# ADAS_ECU_revA.net
KiCad netlist of a schematic drawn in Altium Designer
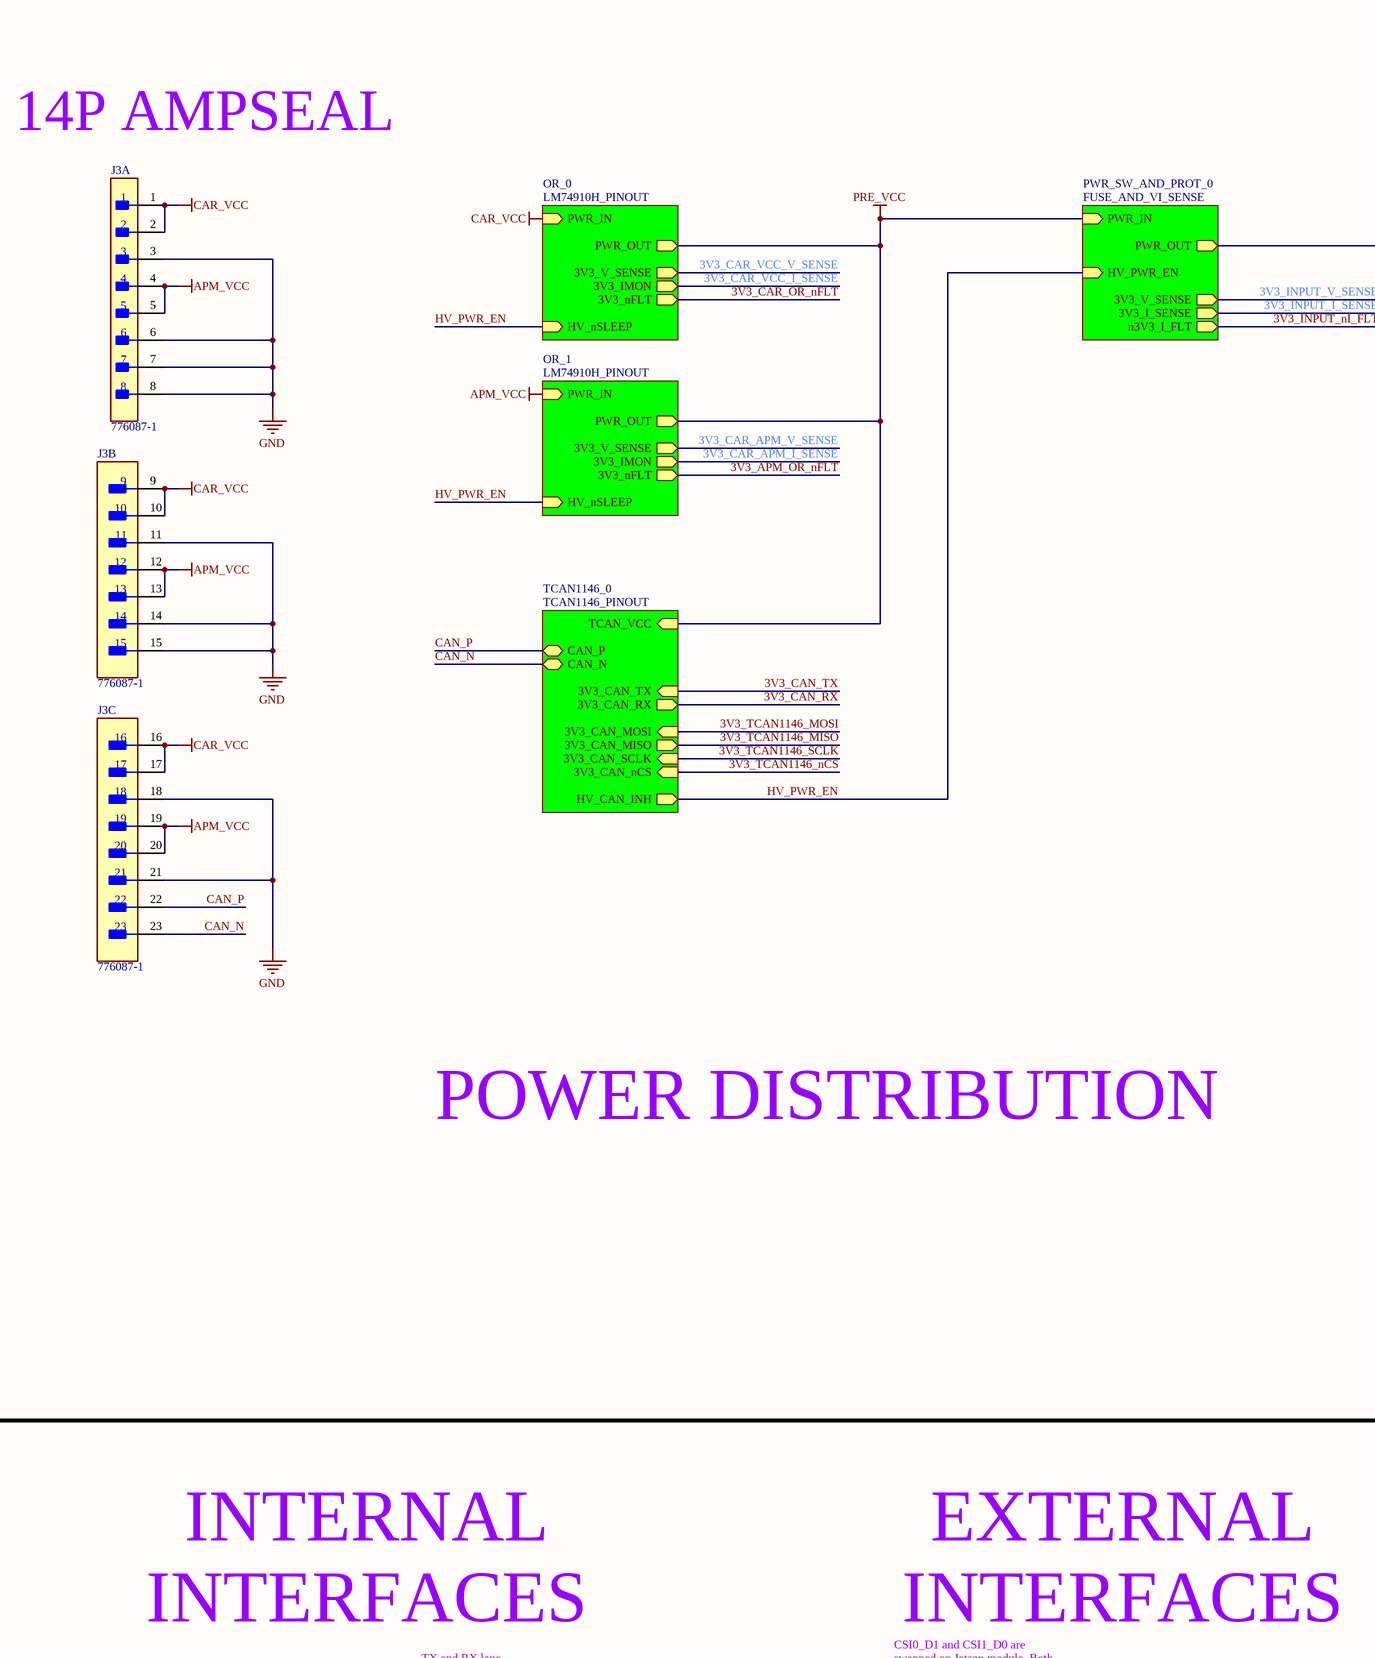
[diagram p0: ADAS_ECU_revA.SchDoc, top column 1 of 4]
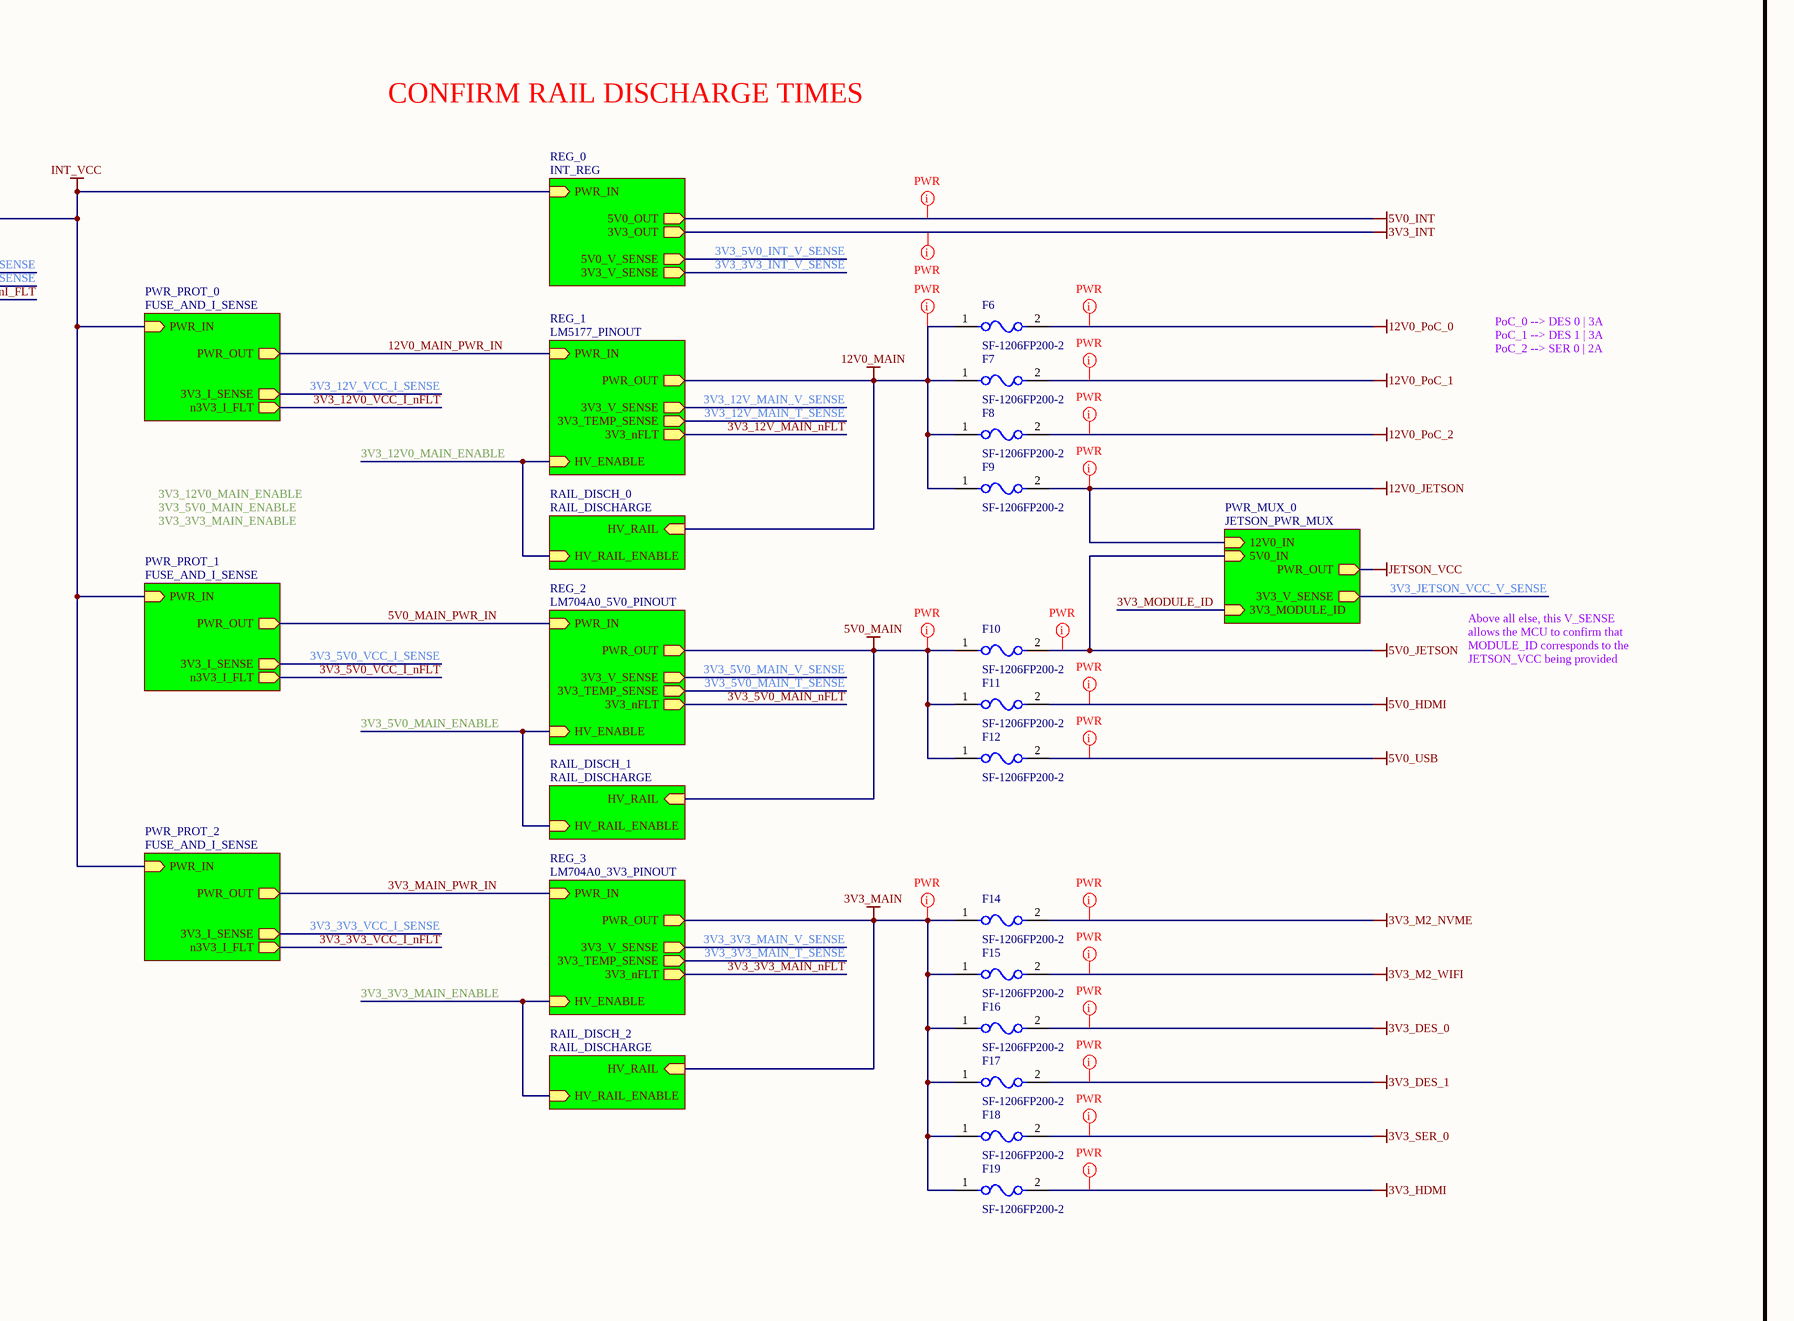
[diagram p1: ADAS_ECU_revA.SchDoc, top column 2 of 4]
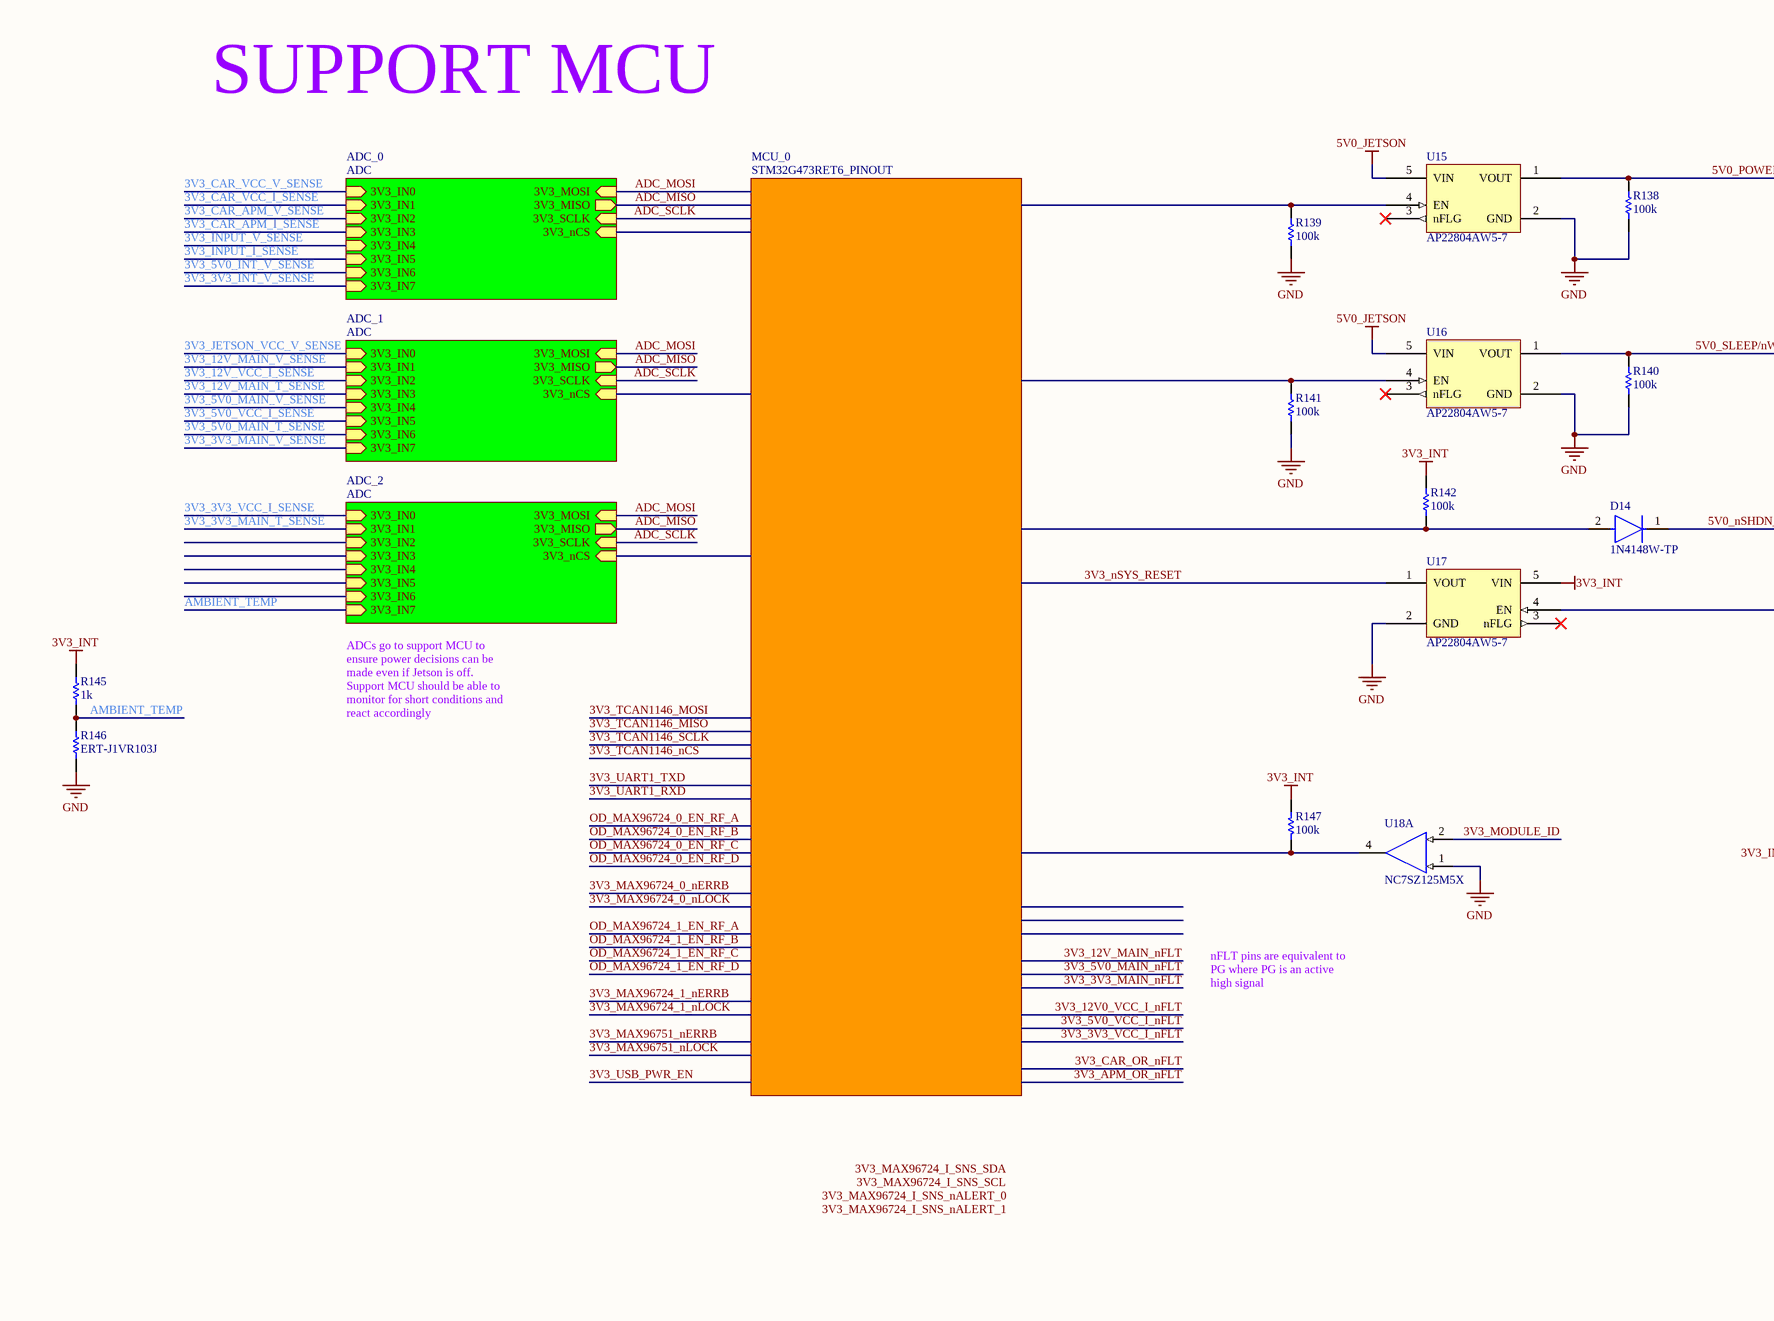
[diagram p2: ADAS_ECU_revA.SchDoc, top column 3 of 4]
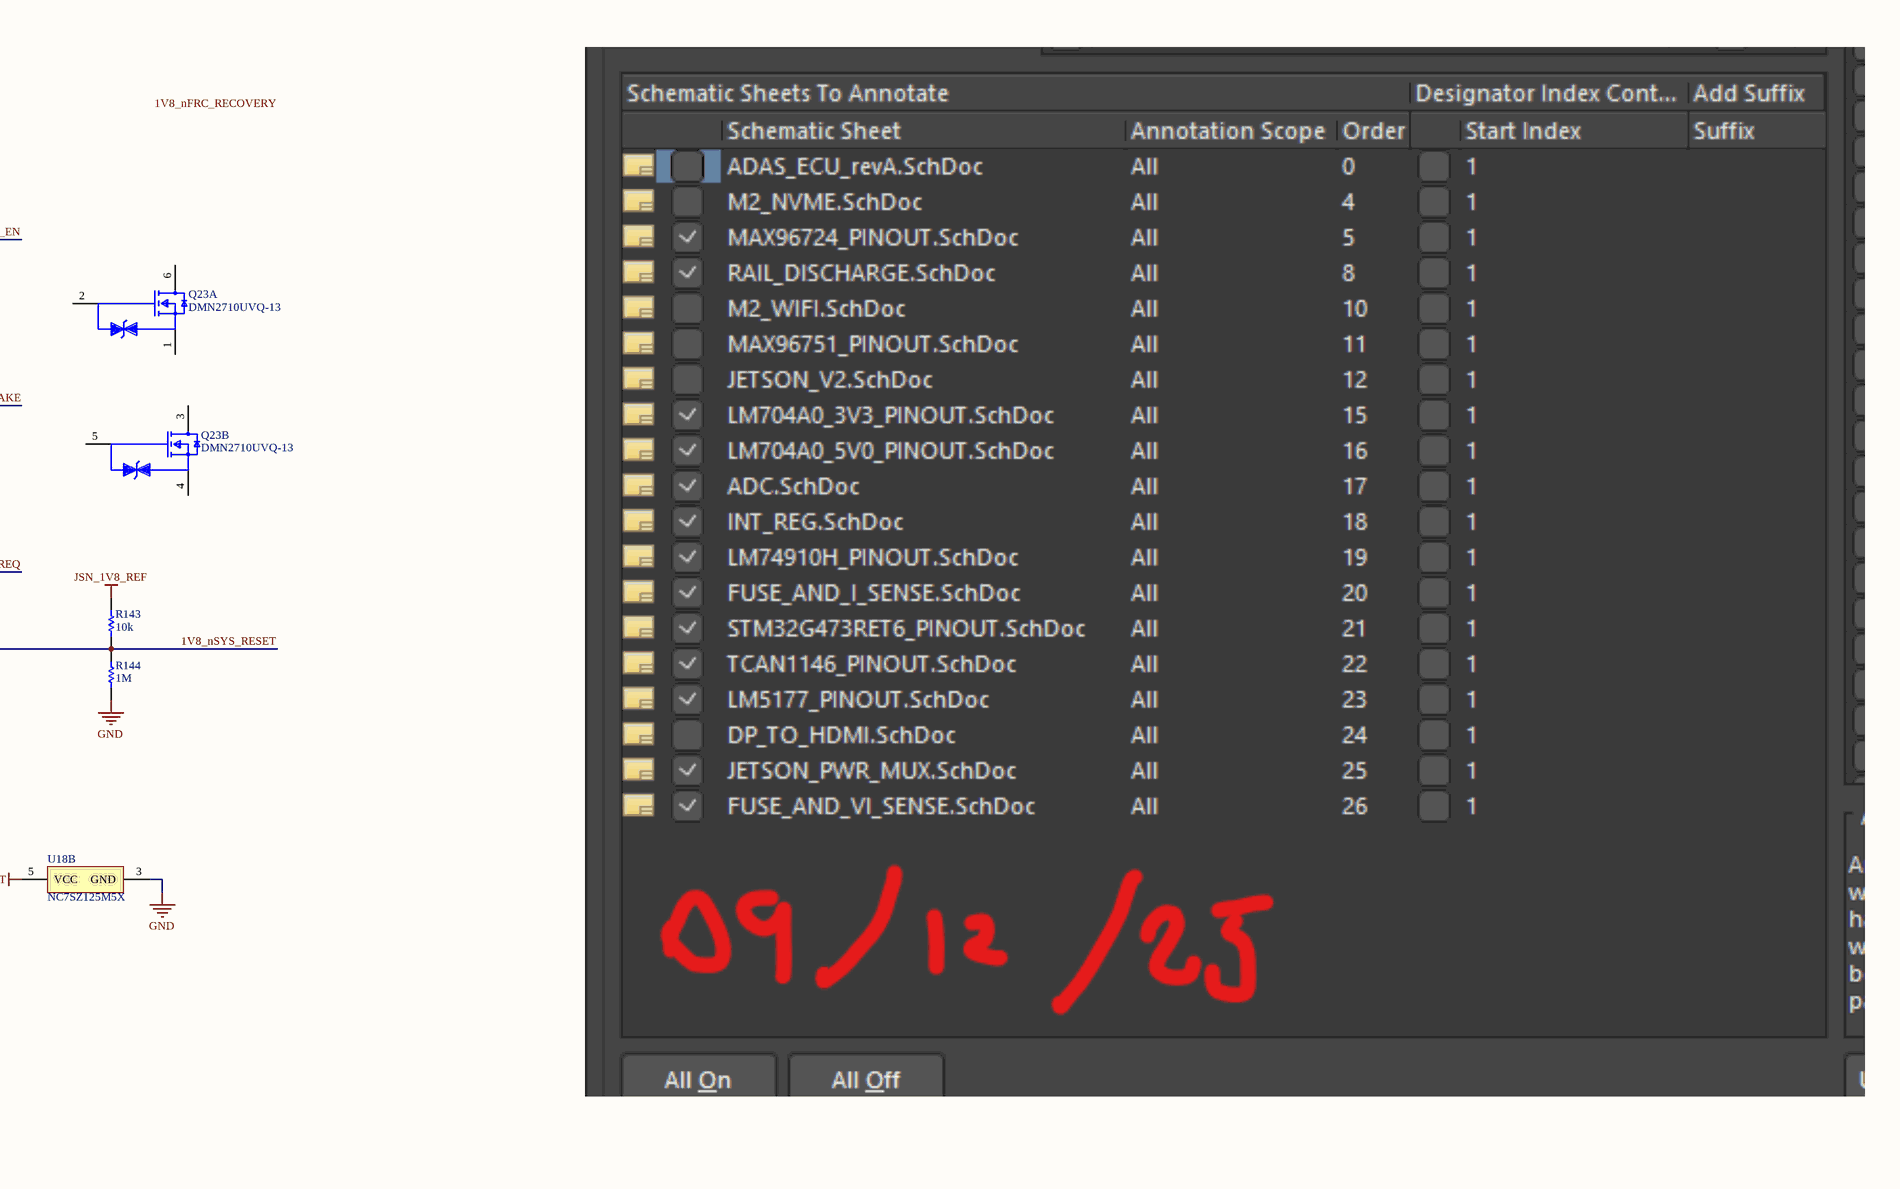
[diagram p3: ADAS_ECU_revA.SchDoc, top column 4 of 4]
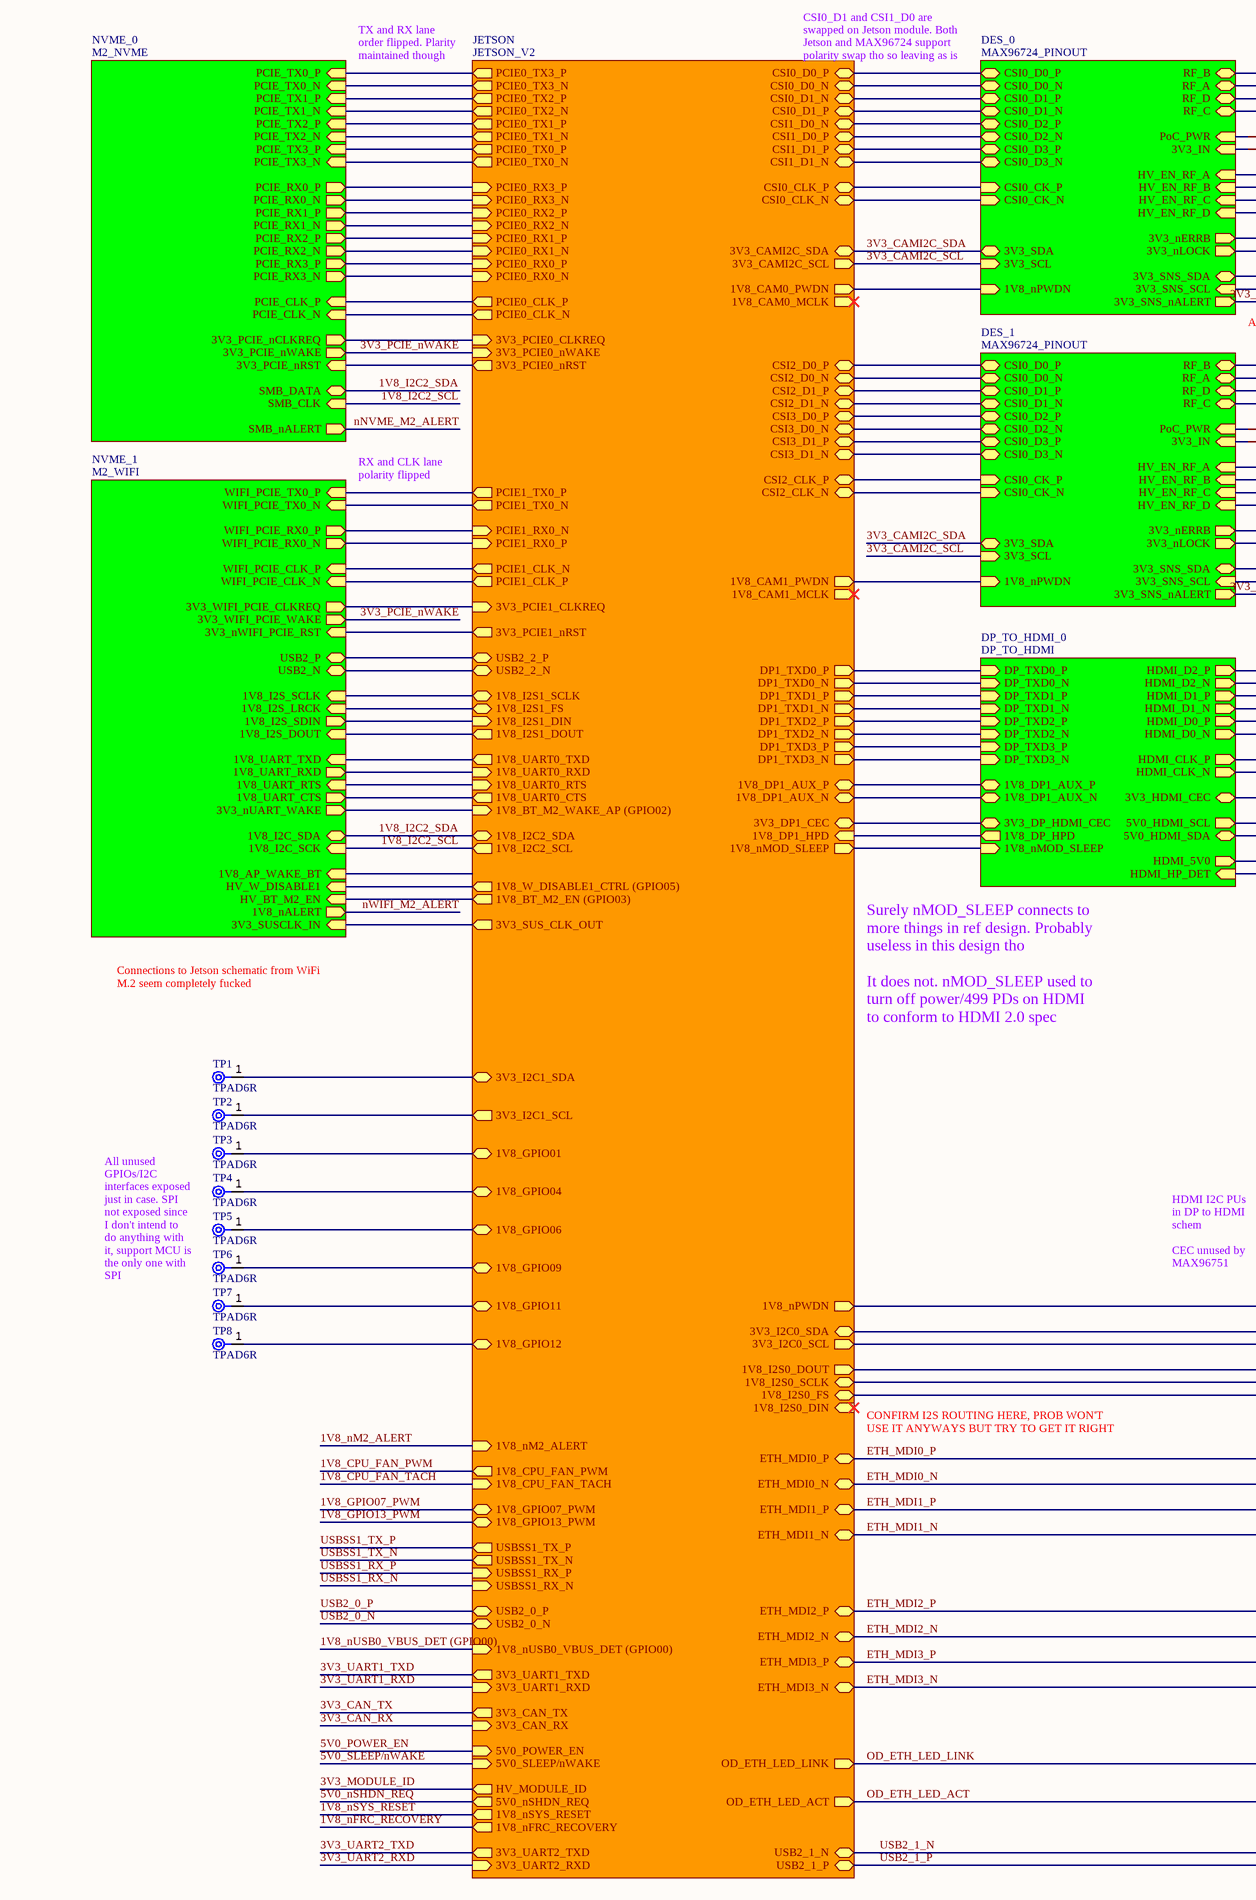
[diagram p4: ADAS_ECU_revA.SchDoc, centre column 1 of 4]
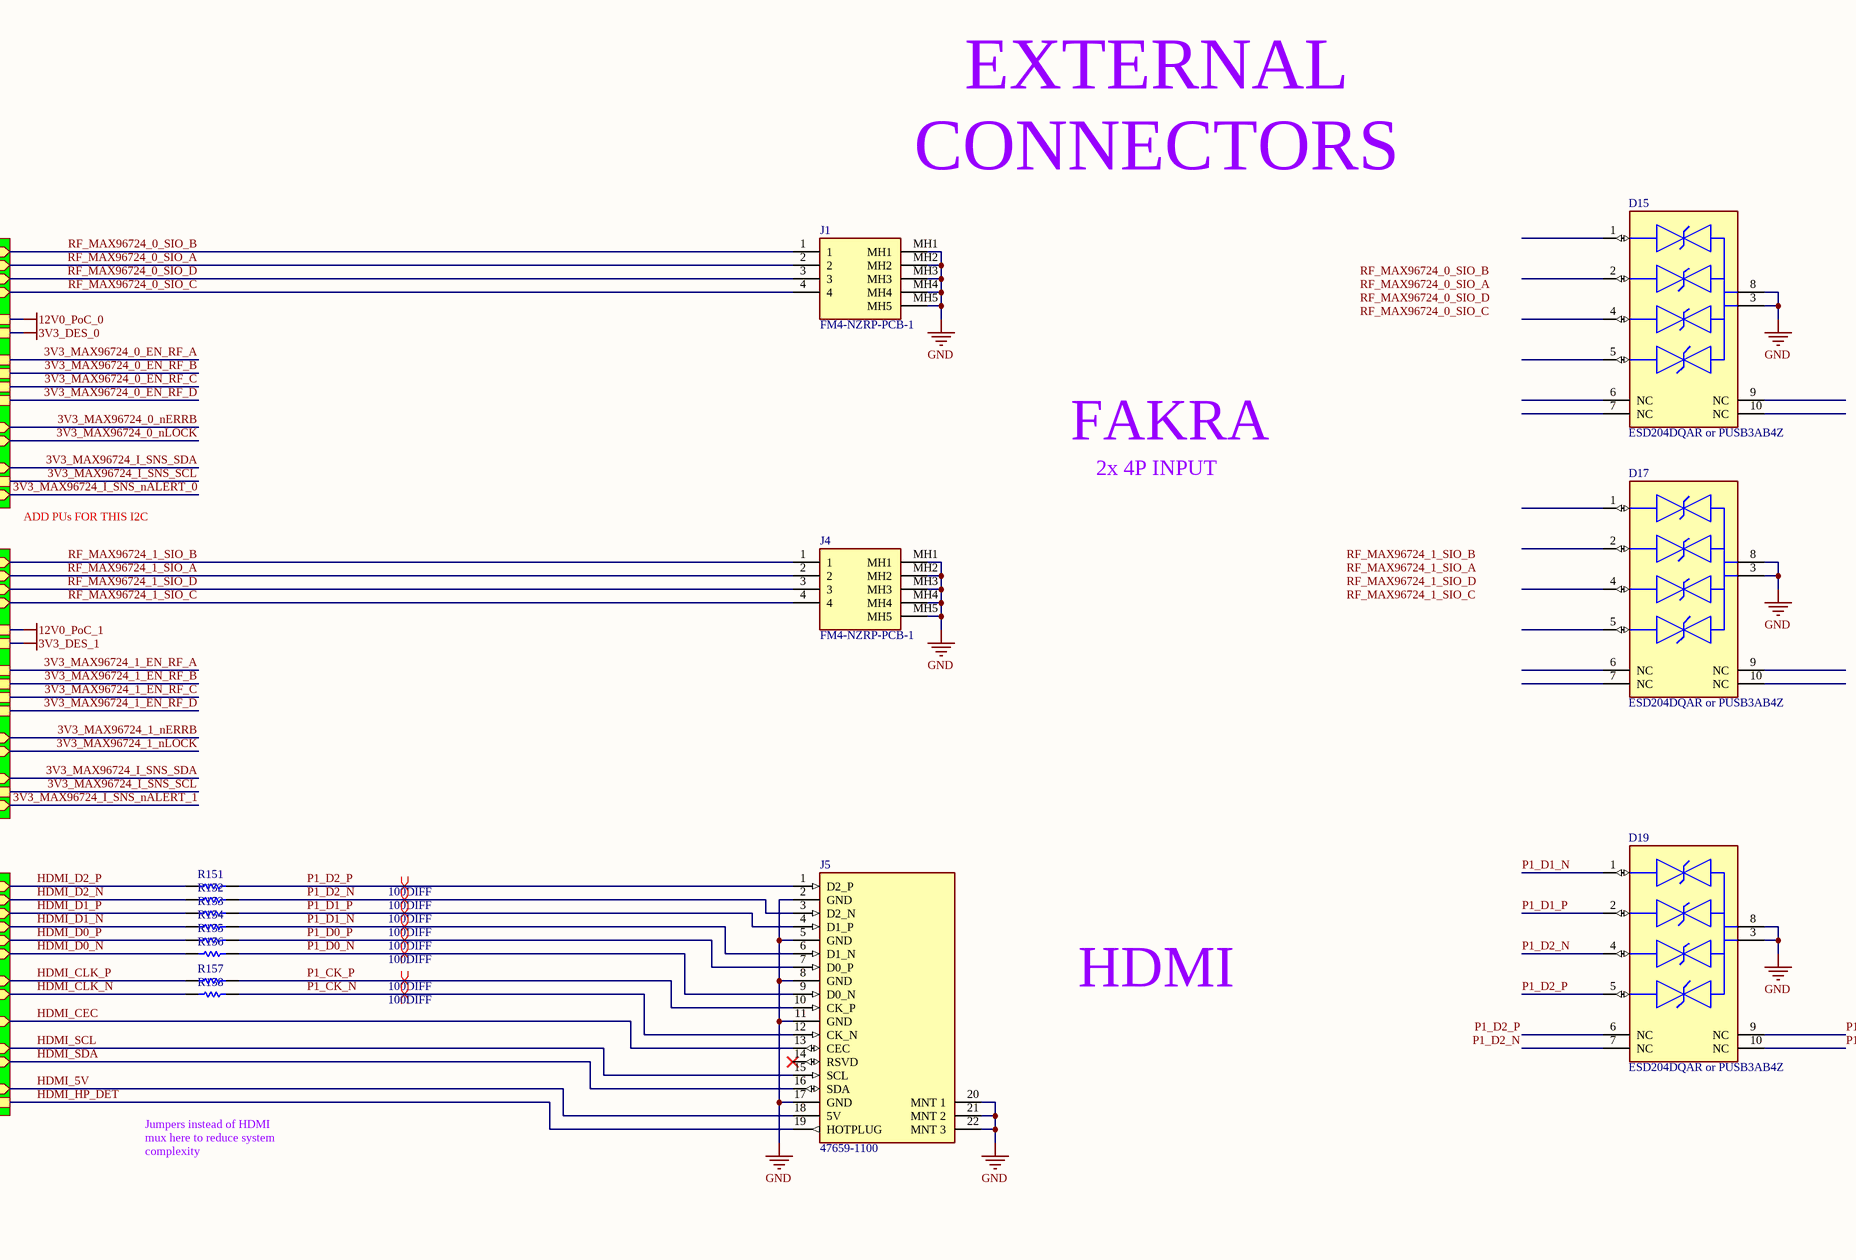
[diagram p5: ADAS_ECU_revA.SchDoc, centre column 2 of 4]
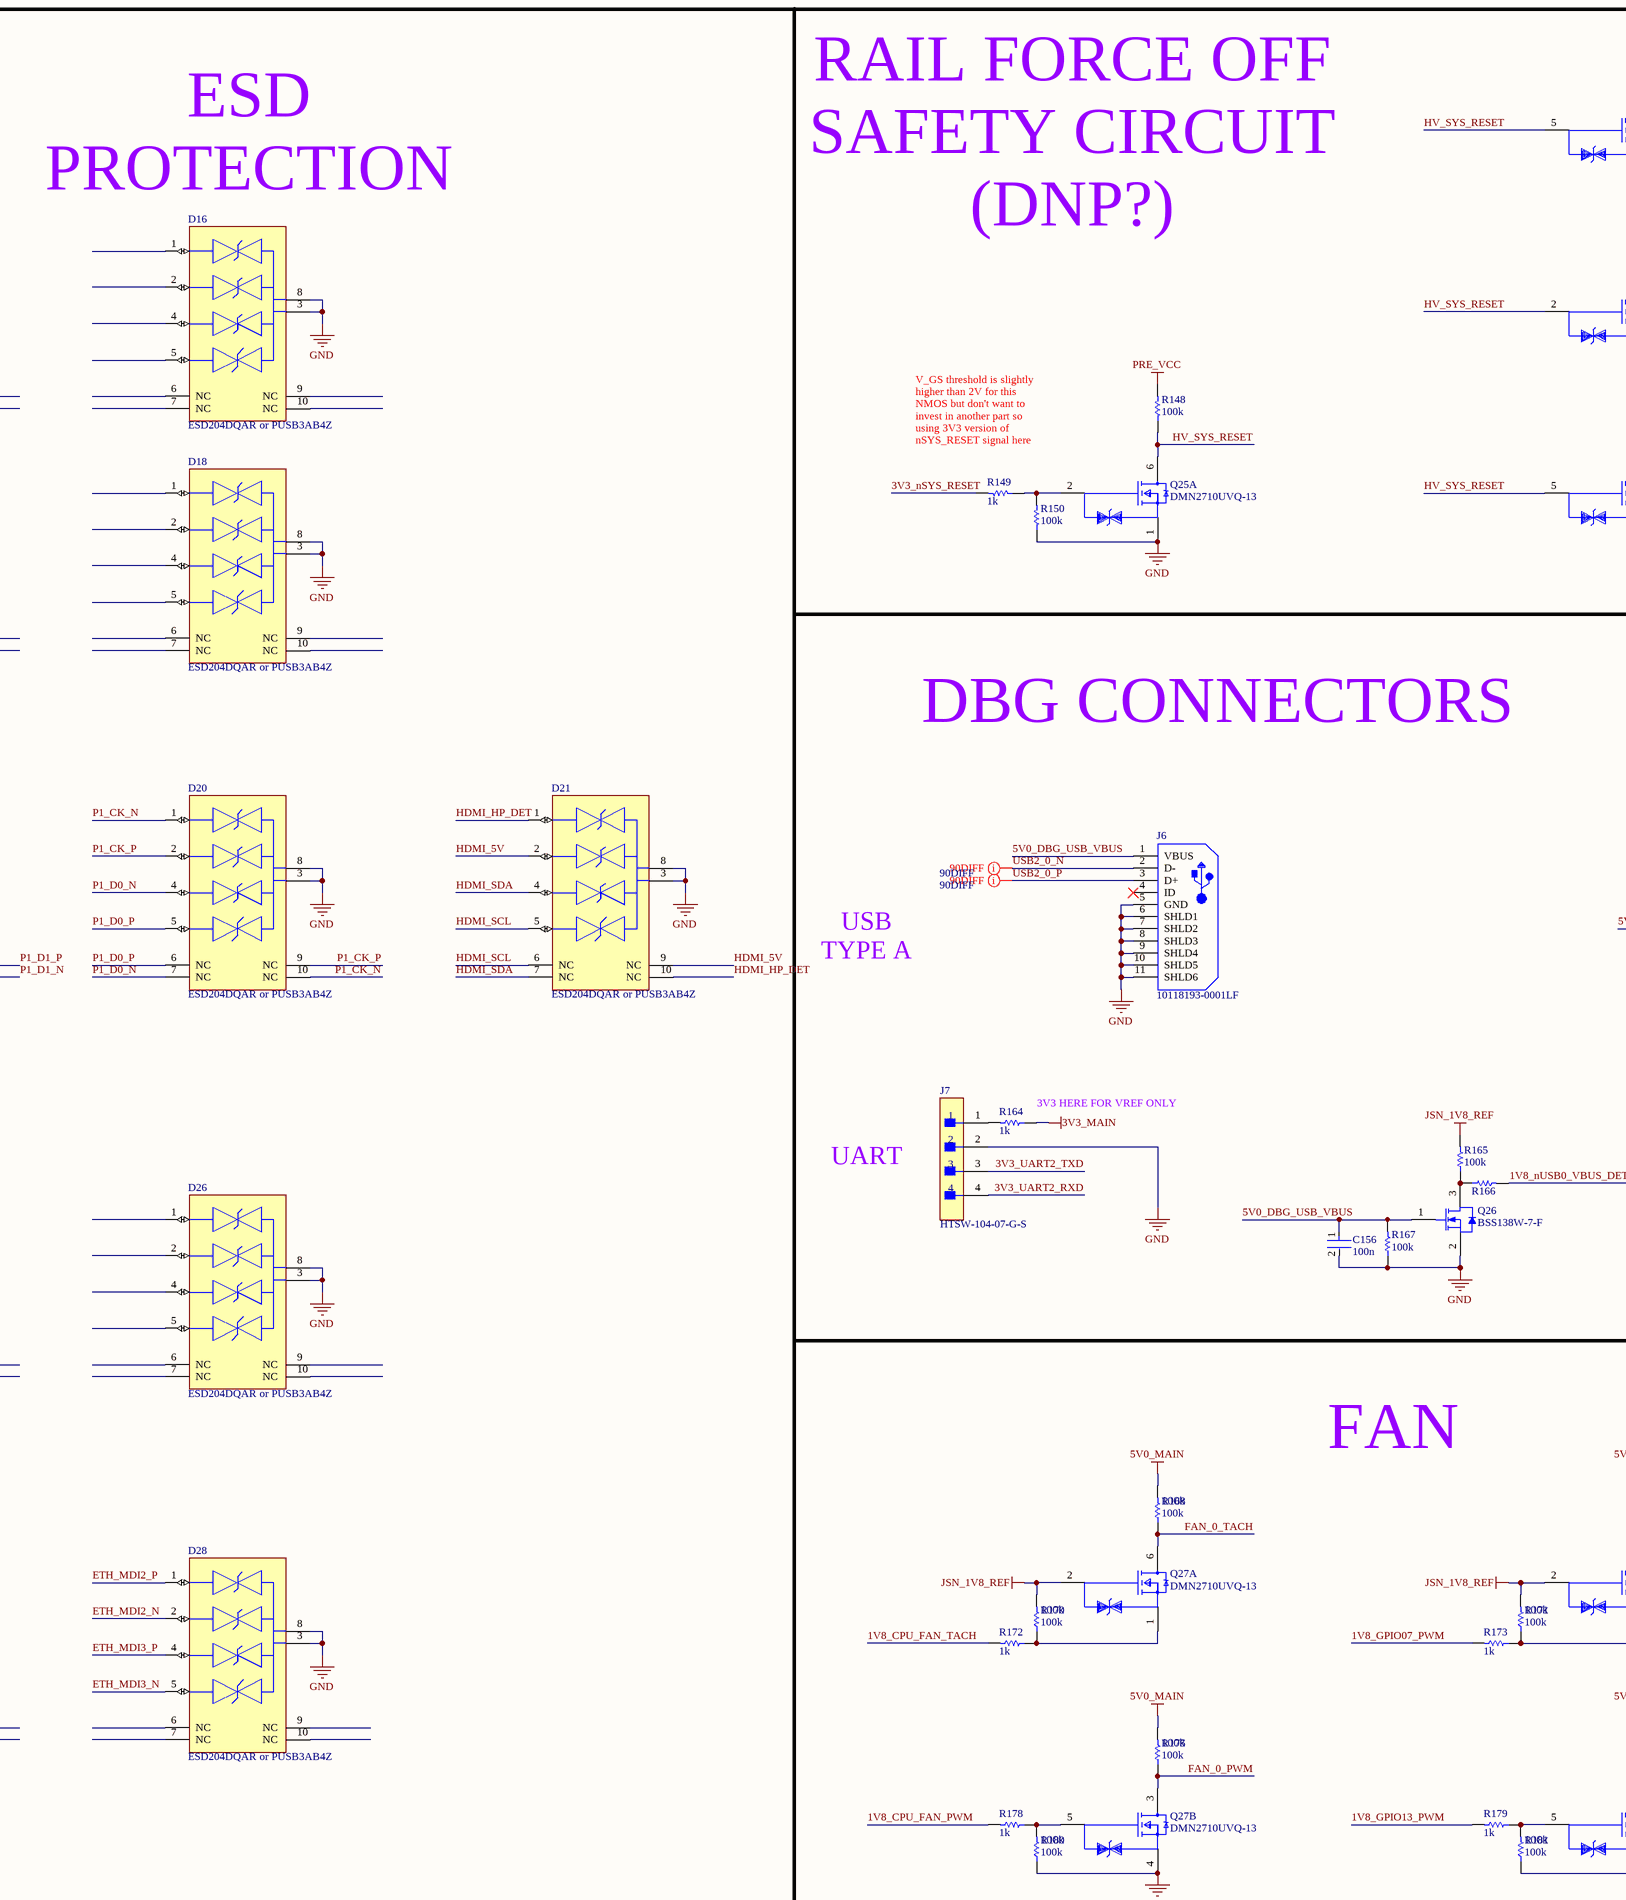
[diagram p6: ADAS_ECU_revA.SchDoc, centre column 3 of 4]
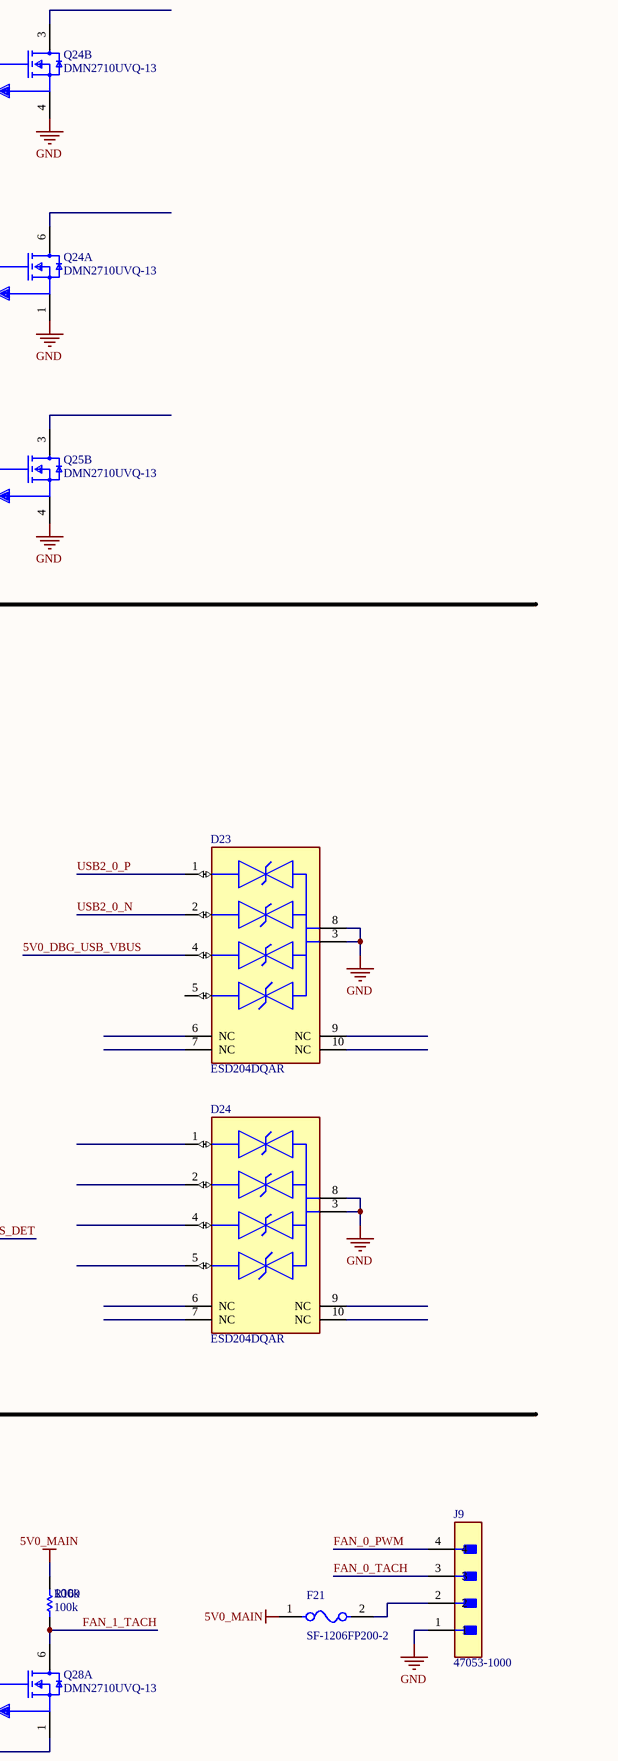
[diagram p7: ADAS_ECU_revA.SchDoc, centre column 4 of 4]
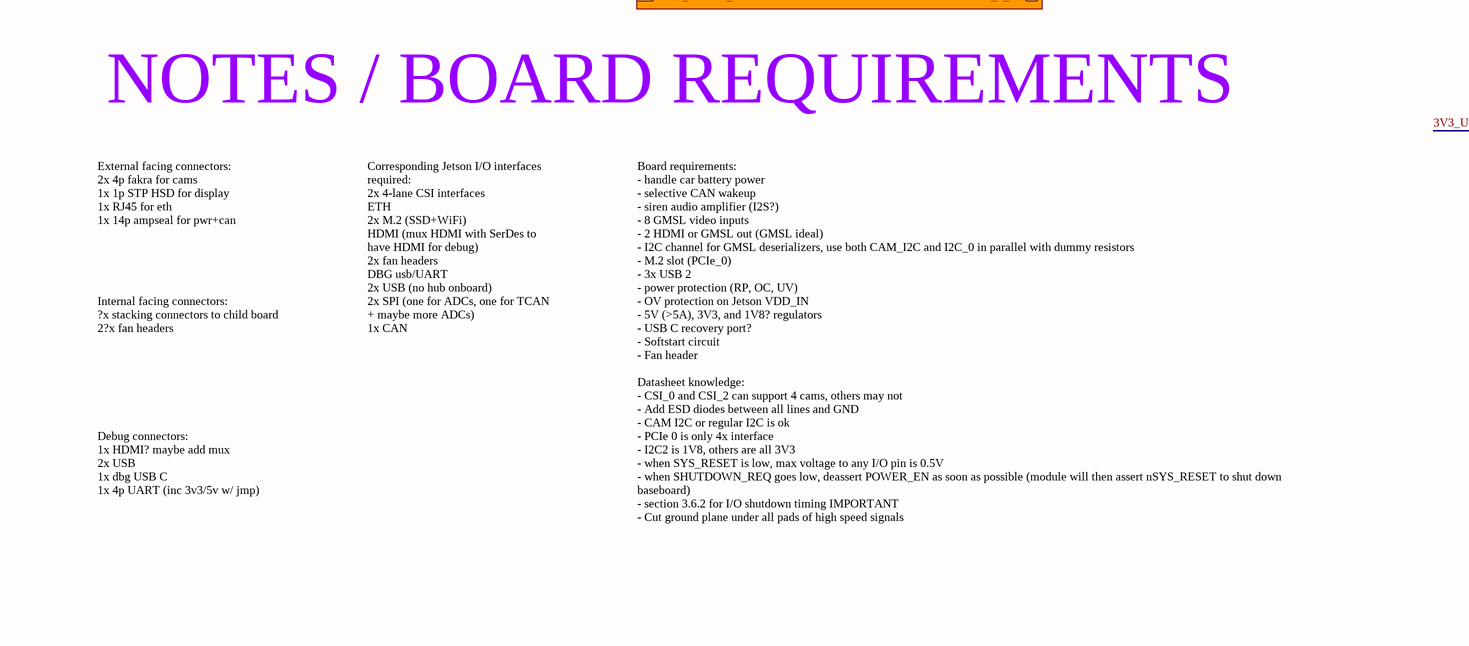
[diagram p8: ADAS_ECU_revA.SchDoc, bottom column 1 of 4]
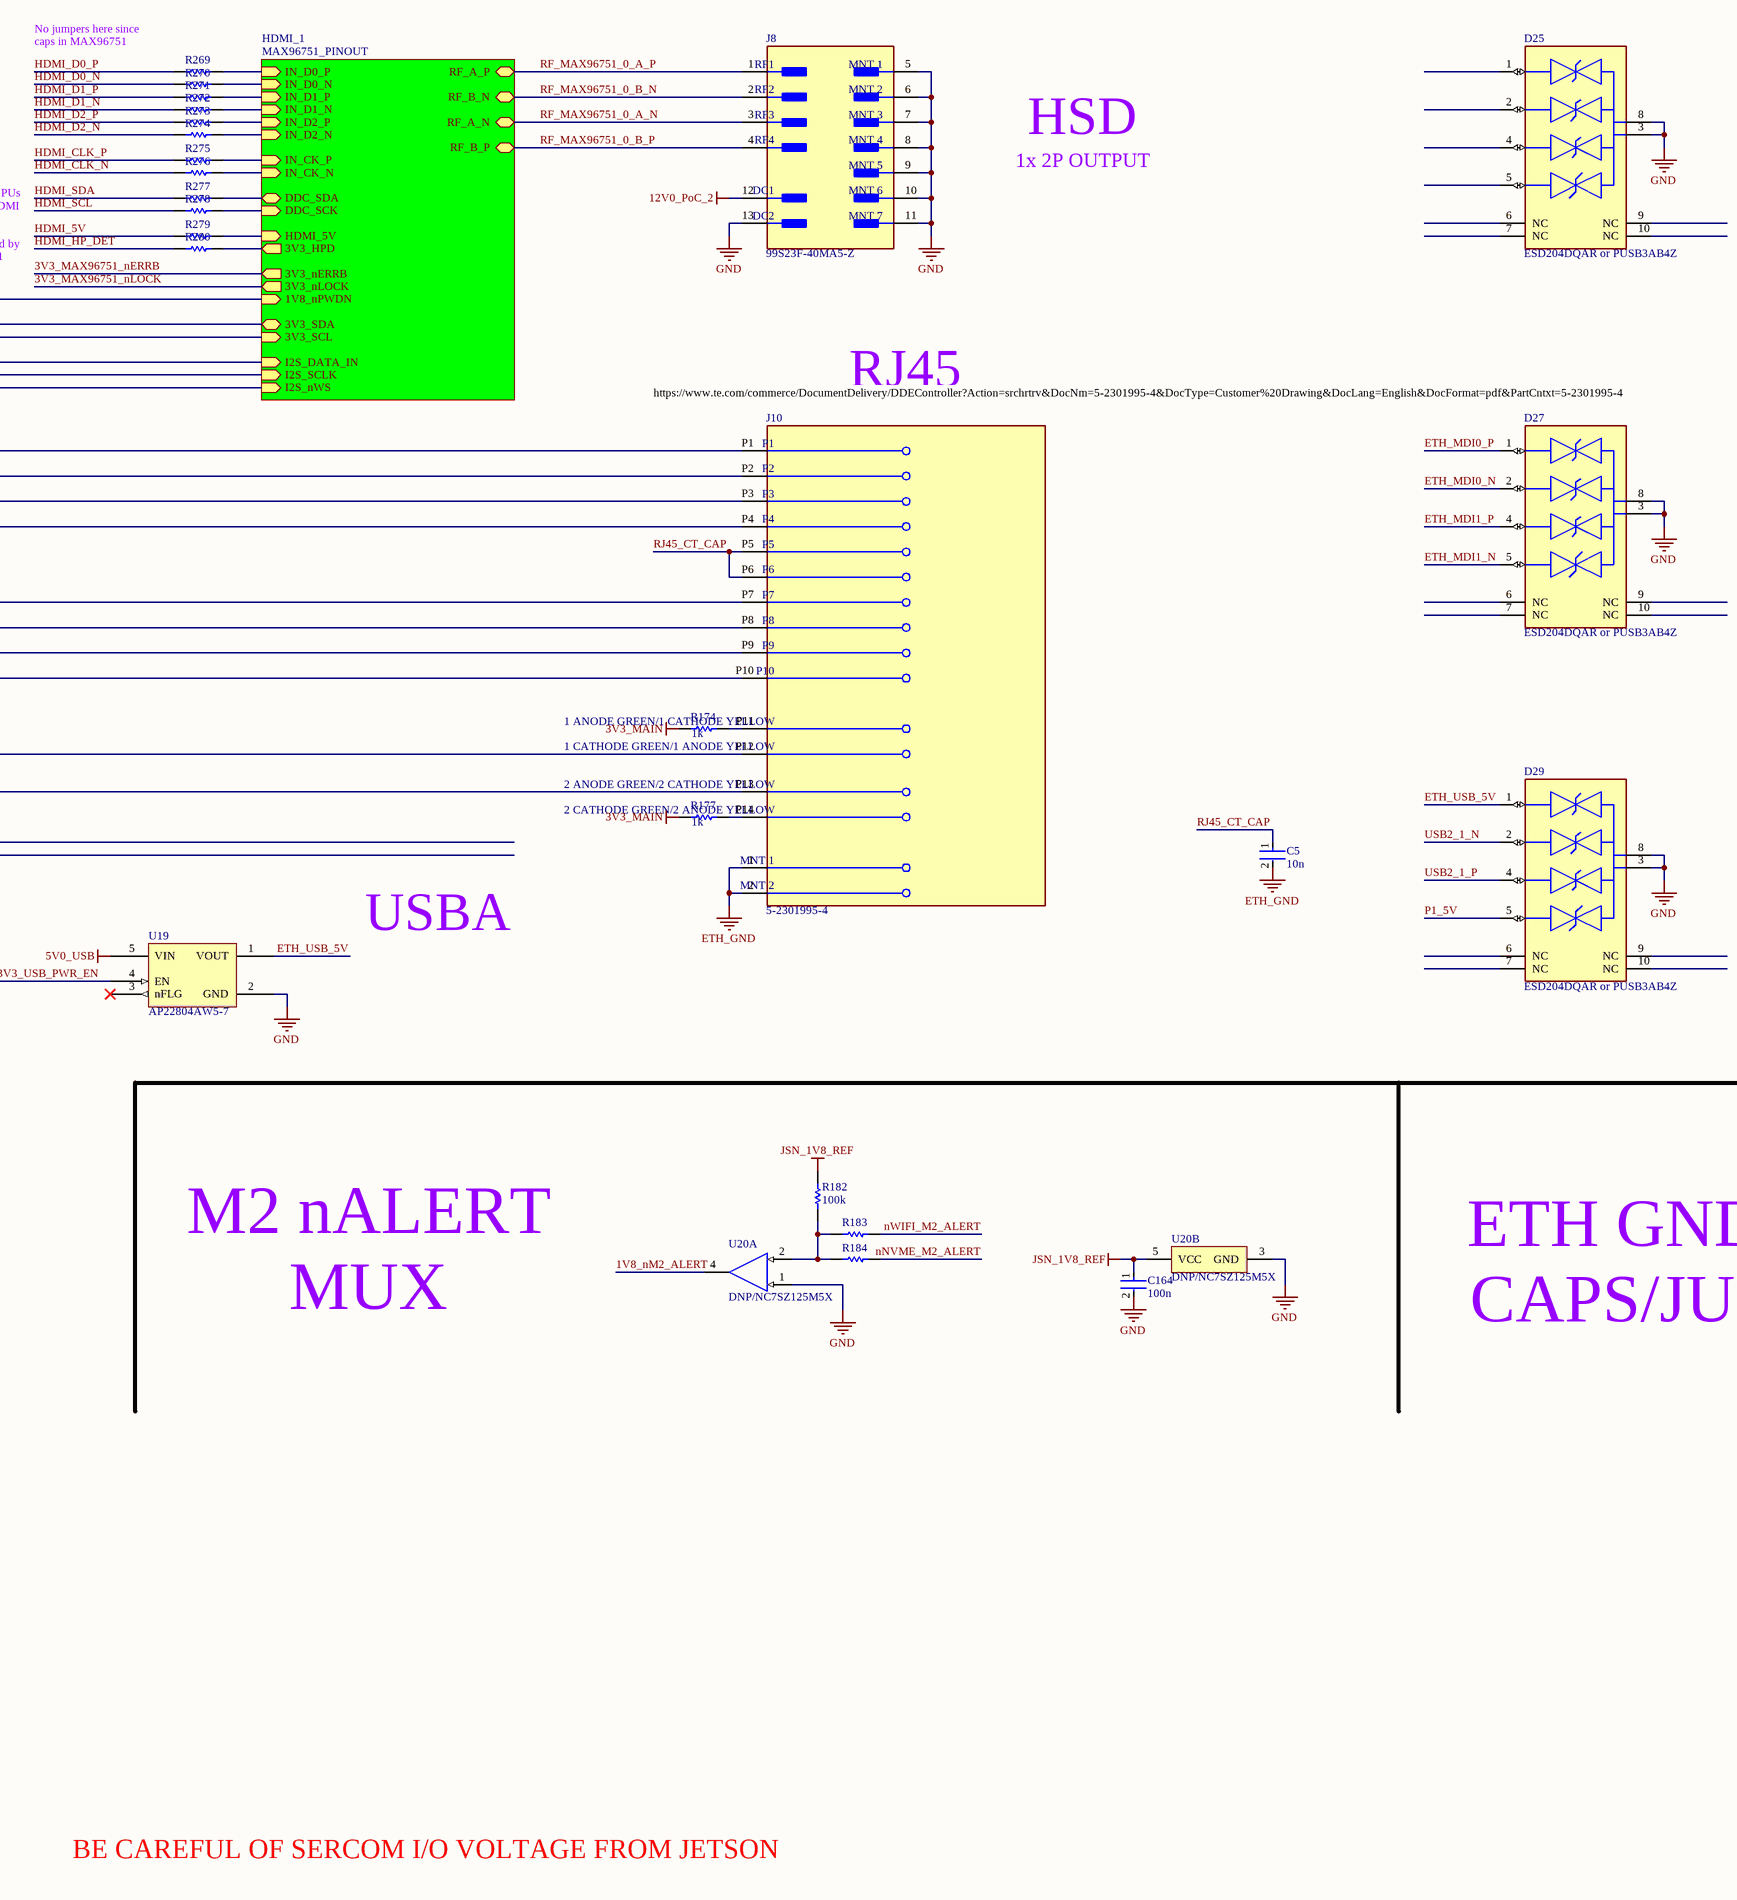
[diagram p9: ADAS_ECU_revA.SchDoc, bottom column 2 of 4]
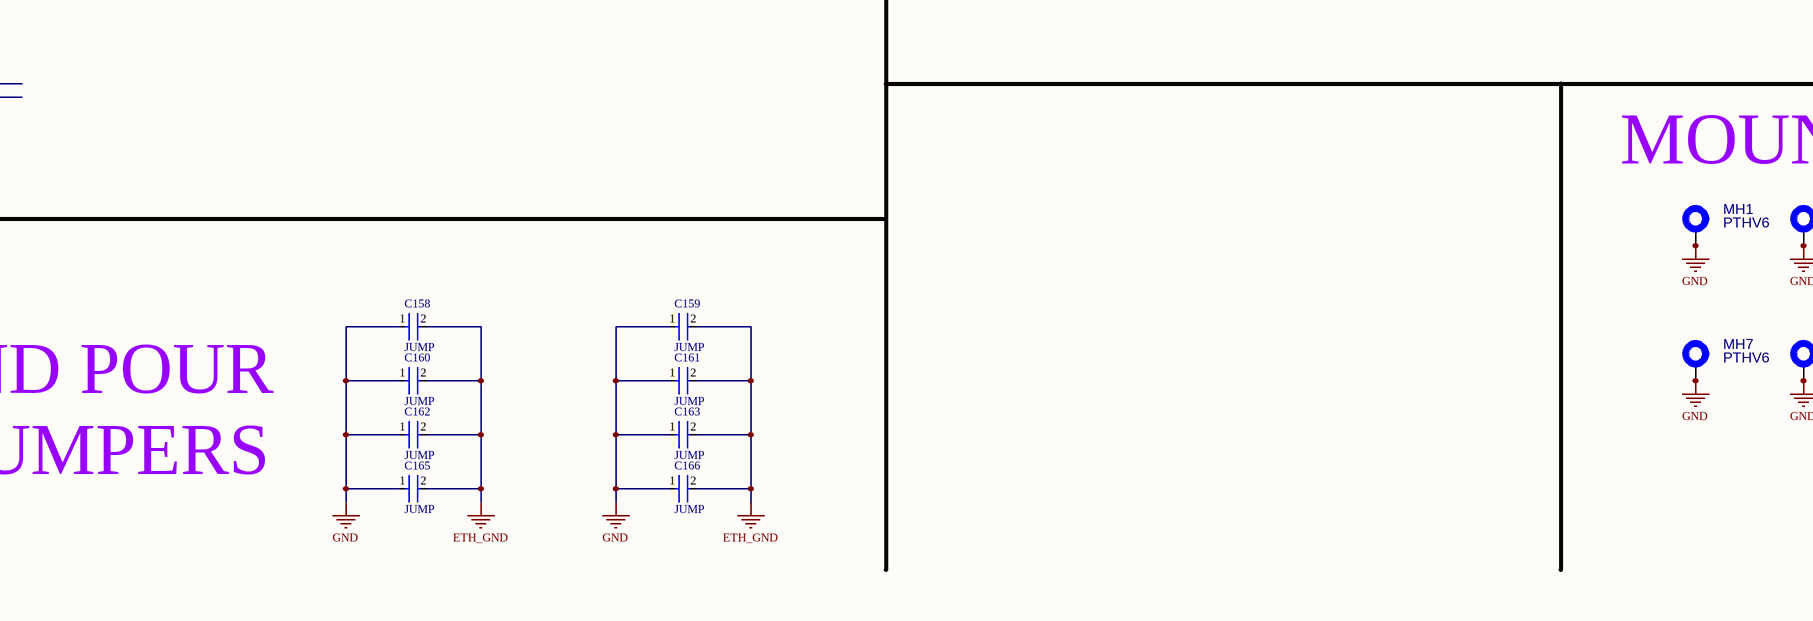
[diagram p10: ADAS_ECU_revA.SchDoc, bottom column 3 of 4]
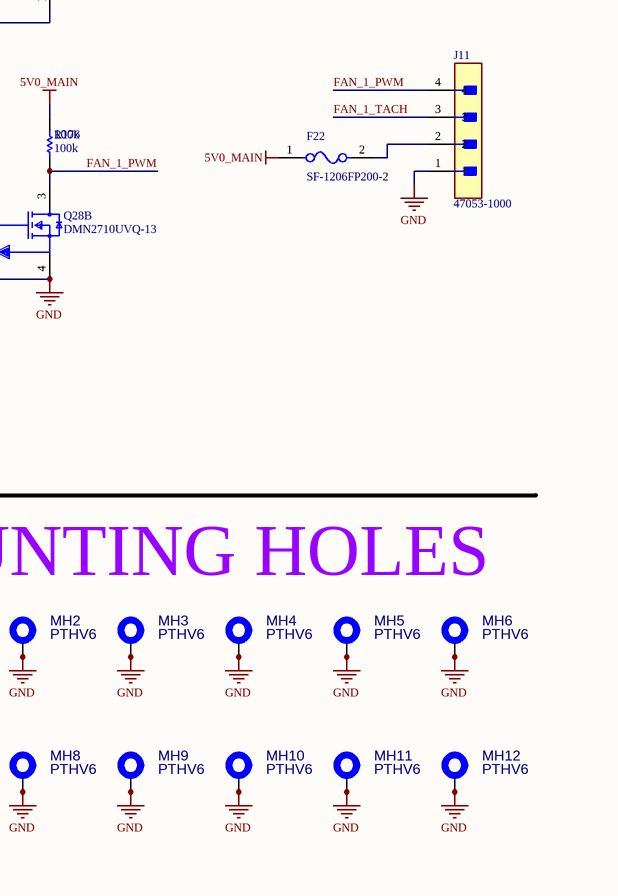
[diagram p11: ADAS_ECU_revA.SchDoc, bottom column 4 of 4]

(export (version "E")
  (design (tool "Eeschema 10.0.6"))
  (components
    (comp (ref "C5")
      (value "10n")
      (footprint "FP-0402-L_1_0_0_05-W_0_5-IPC_A")
      (description "LARGE PADS, 0402 CAP, CHANGE COMMENT TO MATCH REAL P/N")
      (libsource (lib "Space Concordia") (part "b4654b650e69147ec39a6b967a45e02"))
    )
    (comp (ref "C156")
      (value "100n")
      (footprint "FP-0402-L_1_0_0_05-W_0_5-IPC_A")
      (description "LARGE PADS, 0402 CAP, CHANGE COMMENT TO MATCH REAL P/N")
      (libsource (lib "Space Concordia") (part "b4654b650e69147ec39a6b967a45e02"))
    )
    (comp (ref "C158")
      (value "JUMP")
      (footprint "FP-0402-L_1_0_0_05-W_0_5-IPC_A")
      (description "LARGE PADS, 0402 CAP, CHANGE COMMENT TO MATCH REAL P/N")
      (libsource (lib "Space Concordia") (part "b4654b650e69147ec39a6b967a45e02"))
    )
    (comp (ref "C159")
      (value "JUMP")
      (footprint "FP-0402-L_1_0_0_05-W_0_5-IPC_A")
      (description "LARGE PADS, 0402 CAP, CHANGE COMMENT TO MATCH REAL P/N")
      (libsource (lib "Space Concordia") (part "b4654b650e69147ec39a6b967a45e02"))
    )
    (comp (ref "C160")
      (value "JUMP")
      (footprint "FP-0402-L_1_0_0_05-W_0_5-IPC_A")
      (description "LARGE PADS, 0402 CAP, CHANGE COMMENT TO MATCH REAL P/N")
      (libsource (lib "Space Concordia") (part "b4654b650e69147ec39a6b967a45e02"))
    )
    (comp (ref "C161")
      (value "JUMP")
      (footprint "FP-0402-L_1_0_0_05-W_0_5-IPC_A")
      (description "LARGE PADS, 0402 CAP, CHANGE COMMENT TO MATCH REAL P/N")
      (libsource (lib "Space Concordia") (part "b4654b650e69147ec39a6b967a45e02"))
    )
    (comp (ref "C162")
      (value "JUMP")
      (footprint "FP-0402-L_1_0_0_05-W_0_5-IPC_A")
      (description "LARGE PADS, 0402 CAP, CHANGE COMMENT TO MATCH REAL P/N")
      (libsource (lib "Space Concordia") (part "b4654b650e69147ec39a6b967a45e02"))
    )
    (comp (ref "C163")
      (value "JUMP")
      (footprint "FP-0402-L_1_0_0_05-W_0_5-IPC_A")
      (description "LARGE PADS, 0402 CAP, CHANGE COMMENT TO MATCH REAL P/N")
      (libsource (lib "Space Concordia") (part "b4654b650e69147ec39a6b967a45e02"))
    )
    (comp (ref "C164")
      (value "100n")
      (footprint "FP-0402-L_1_0_0_05-W_0_5-IPC_A")
      (description "LARGE PADS, 0402 CAP, CHANGE COMMENT TO MATCH REAL P/N")
      (libsource (lib "Space Concordia") (part "b4654b650e69147ec39a6b967a45e02"))
    )
    (comp (ref "C165")
      (value "JUMP")
      (footprint "FP-0402-L_1_0_0_05-W_0_5-IPC_A")
      (description "LARGE PADS, 0402 CAP, CHANGE COMMENT TO MATCH REAL P/N")
      (libsource (lib "Space Concordia") (part "b4654b650e69147ec39a6b967a45e02"))
    )
    (comp (ref "C166")
      (value "JUMP")
      (footprint "FP-0402-L_1_0_0_05-W_0_5-IPC_A")
      (description "LARGE PADS, 0402 CAP, CHANGE COMMENT TO MATCH REAL P/N")
      (libsource (lib "Space Concordia") (part "b4654b650e69147ec39a6b967a45e02"))
    )
    (comp (ref "D14")
      (value "1N4148W-TP")
      (footprint "FP-SOD-123-IPC_A")
      (description "DIODE GEN PURP 100V 150MA SOD123")
      (libsource (lib "Altium Content Vault") (part "d7152d700b627762746794eb795d46e"))
    )
    (comp (ref "D15")
      (value "ESD204DQAR or PUSB3AB4Z")
      (footprint "FP-DQA0010A-MFG")
      (description "4-CHANNEL LOW-CAPACITANCE SURGE")
      (fields
        (field (name "MANUFACTURER") "Texas Instruments")
        (field (name "OCTOPART") "https://octopart.com/esd204dqar-texas+instruments-89917476")
      )
      (libsource (lib "Altium Content Vault") (part "1465e58c1818c7767b55926832f0bf5"))
    )
    (comp (ref "D16")
      (value "ESD204DQAR or PUSB3AB4Z")
      (footprint "FP-DQA0010A-MFG")
      (description "4-CHANNEL LOW-CAPACITANCE SURGE")
      (fields
        (field (name "MANUFACTURER") "Texas Instruments")
        (field (name "OCTOPART") "https://octopart.com/esd204dqar-texas+instruments-89917476")
      )
      (libsource (lib "Altium Content Vault") (part "1465e58c1818c7767b55926832f0bf5"))
    )
    (comp (ref "D17")
      (value "ESD204DQAR or PUSB3AB4Z")
      (footprint "FP-DQA0010A-MFG")
      (description "4-CHANNEL LOW-CAPACITANCE SURGE")
      (fields
        (field (name "MANUFACTURER") "Texas Instruments")
        (field (name "OCTOPART") "https://octopart.com/esd204dqar-texas+instruments-89917476")
      )
      (libsource (lib "Altium Content Vault") (part "1465e58c1818c7767b55926832f0bf5"))
    )
    (comp (ref "D18")
      (value "ESD204DQAR or PUSB3AB4Z")
      (footprint "FP-DQA0010A-MFG")
      (description "4-CHANNEL LOW-CAPACITANCE SURGE")
      (fields
        (field (name "MANUFACTURER") "Texas Instruments")
        (field (name "OCTOPART") "https://octopart.com/esd204dqar-texas+instruments-89917476")
      )
      (libsource (lib "Altium Content Vault") (part "1465e58c1818c7767b55926832f0bf5"))
    )
    (comp (ref "D19")
      (value "ESD204DQAR or PUSB3AB4Z")
      (footprint "FP-DQA0010A-MFG")
      (description "4-CHANNEL LOW-CAPACITANCE SURGE")
      (fields
        (field (name "MANUFACTURER") "Texas Instruments")
        (field (name "OCTOPART") "https://octopart.com/esd204dqar-texas+instruments-89917476")
      )
      (libsource (lib "Altium Content Vault") (part "1465e58c1818c7767b55926832f0bf5"))
    )
    (comp (ref "D20")
      (value "ESD204DQAR or PUSB3AB4Z")
      (footprint "FP-DQA0010A-MFG")
      (description "4-CHANNEL LOW-CAPACITANCE SURGE")
      (fields
        (field (name "MANUFACTURER") "Texas Instruments")
        (field (name "OCTOPART") "https://octopart.com/esd204dqar-texas+instruments-89917476")
      )
      (libsource (lib "Altium Content Vault") (part "1465e58c1818c7767b55926832f0bf5"))
    )
    (comp (ref "D21")
      (value "ESD204DQAR or PUSB3AB4Z")
      (footprint "FP-DQA0010A-MFG")
      (description "4-CHANNEL LOW-CAPACITANCE SURGE")
      (fields
        (field (name "MANUFACTURER") "Texas Instruments")
        (field (name "OCTOPART") "https://octopart.com/esd204dqar-texas+instruments-89917476")
      )
      (libsource (lib "Altium Content Vault") (part "1465e58c1818c7767b55926832f0bf5"))
    )
    (comp (ref "D23")
      (value "ESD204DQAR")
      (footprint "FP-DQA0010A-MFG")
      (description "4-CHANNEL LOW-CAPACITANCE SURGE")
      (fields
        (field (name "MANUFACTURER") "Texas Instruments")
        (field (name "OCTOPART") "https://octopart.com/esd204dqar-texas+instruments-89917476")
      )
      (libsource (lib "Altium Content Vault") (part "1465e58c1818c7767b55926832f0bf5"))
    )
    (comp (ref "D24")
      (value "ESD204DQAR")
      (footprint "FP-DQA0010A-MFG")
      (description "4-CHANNEL LOW-CAPACITANCE SURGE")
      (fields
        (field (name "MANUFACTURER") "Texas Instruments")
        (field (name "OCTOPART") "https://octopart.com/esd204dqar-texas+instruments-89917476")
      )
      (libsource (lib "Altium Content Vault") (part "1465e58c1818c7767b55926832f0bf5"))
    )
    (comp (ref "D25")
      (value "ESD204DQAR or PUSB3AB4Z")
      (footprint "FP-DQA0010A-MFG")
      (description "4-CHANNEL LOW-CAPACITANCE SURGE")
      (fields
        (field (name "MANUFACTURER") "Texas Instruments")
        (field (name "OCTOPART") "https://octopart.com/esd204dqar-texas+instruments-89917476")
      )
      (libsource (lib "Altium Content Vault") (part "1465e58c1818c7767b55926832f0bf5"))
    )
    (comp (ref "D26")
      (value "ESD204DQAR or PUSB3AB4Z")
      (footprint "FP-DQA0010A-MFG")
      (description "4-CHANNEL LOW-CAPACITANCE SURGE")
      (fields
        (field (name "MANUFACTURER") "Texas Instruments")
        (field (name "OCTOPART") "https://octopart.com/esd204dqar-texas+instruments-89917476")
      )
      (libsource (lib "Altium Content Vault") (part "1465e58c1818c7767b55926832f0bf5"))
    )
    (comp (ref "D27")
      (value "ESD204DQAR or PUSB3AB4Z")
      (footprint "FP-DQA0010A-MFG")
      (description "4-CHANNEL LOW-CAPACITANCE SURGE")
      (fields
        (field (name "MANUFACTURER") "Texas Instruments")
        (field (name "OCTOPART") "https://octopart.com/esd204dqar-texas+instruments-89917476")
      )
      (libsource (lib "Altium Content Vault") (part "1465e58c1818c7767b55926832f0bf5"))
    )
    (comp (ref "D28")
      (value "ESD204DQAR or PUSB3AB4Z")
      (footprint "FP-DQA0010A-MFG")
      (description "4-CHANNEL LOW-CAPACITANCE SURGE")
      (fields
        (field (name "MANUFACTURER") "Texas Instruments")
        (field (name "OCTOPART") "https://octopart.com/esd204dqar-texas+instruments-89917476")
      )
      (libsource (lib "Altium Content Vault") (part "1465e58c1818c7767b55926832f0bf5"))
    )
    (comp (ref "D29")
      (value "ESD204DQAR or PUSB3AB4Z")
      (footprint "FP-DQA0010A-MFG")
      (description "4-CHANNEL LOW-CAPACITANCE SURGE")
      (fields
        (field (name "MANUFACTURER") "Texas Instruments")
        (field (name "OCTOPART") "https://octopart.com/esd204dqar-texas+instruments-89917476")
      )
      (libsource (lib "Altium Content Vault") (part "1465e58c1818c7767b55926832f0bf5"))
    )
    (comp (ref "F6")
      (value "SF-1206FP200-2")
      (footprint "FP-SF-1206FP-MFG")
      (description "FUSE BOARD MOUNT 2A 63VDC 1206")
      (libsource (lib "Altium Content Vault") (part "5bcf9b9f640e542cf0359d10258e979"))
    )
    (comp (ref "F7")
      (value "SF-1206FP200-2")
      (footprint "FP-SF-1206FP-MFG")
      (description "FUSE BOARD MOUNT 2A 63VDC 1206")
      (libsource (lib "Altium Content Vault") (part "5bcf9b9f640e542cf0359d10258e979"))
    )
    (comp (ref "F8")
      (value "SF-1206FP200-2")
      (footprint "FP-SF-1206FP-MFG")
      (description "FUSE BOARD MOUNT 2A 63VDC 1206")
      (libsource (lib "Altium Content Vault") (part "5bcf9b9f640e542cf0359d10258e979"))
    )
    (comp (ref "F9")
      (value "SF-1206FP200-2")
      (footprint "FP-SF-1206FP-MFG")
      (description "FUSE BOARD MOUNT 2A 63VDC 1206")
      (libsource (lib "Altium Content Vault") (part "5bcf9b9f640e542cf0359d10258e979"))
    )
    (comp (ref "F10")
      (value "SF-1206FP200-2")
      (footprint "FP-SF-1206FP-MFG")
      (description "FUSE BOARD MOUNT 2A 63VDC 1206")
      (libsource (lib "Altium Content Vault") (part "5bcf9b9f640e542cf0359d10258e979"))
    )
    (comp (ref "F11")
      (value "SF-1206FP200-2")
      (footprint "FP-SF-1206FP-MFG")
      (description "FUSE BOARD MOUNT 2A 63VDC 1206")
      (libsource (lib "Altium Content Vault") (part "5bcf9b9f640e542cf0359d10258e979"))
    )
    (comp (ref "F12")
      (value "SF-1206FP200-2")
      (footprint "FP-SF-1206FP-MFG")
      (description "FUSE BOARD MOUNT 2A 63VDC 1206")
      (libsource (lib "Altium Content Vault") (part "5bcf9b9f640e542cf0359d10258e979"))
    )
    (comp (ref "F14")
      (value "SF-1206FP200-2")
      (footprint "FP-SF-1206FP-MFG")
      (description "FUSE BOARD MOUNT 2A 63VDC 1206")
      (libsource (lib "Altium Content Vault") (part "5bcf9b9f640e542cf0359d10258e979"))
    )
    (comp (ref "F15")
      (value "SF-1206FP200-2")
      (footprint "FP-SF-1206FP-MFG")
      (description "FUSE BOARD MOUNT 2A 63VDC 1206")
      (libsource (lib "Altium Content Vault") (part "5bcf9b9f640e542cf0359d10258e979"))
    )
    (comp (ref "F16")
      (value "SF-1206FP200-2")
      (footprint "FP-SF-1206FP-MFG")
      (description "FUSE BOARD MOUNT 2A 63VDC 1206")
      (libsource (lib "Altium Content Vault") (part "5bcf9b9f640e542cf0359d10258e979"))
    )
    (comp (ref "F17")
      (value "SF-1206FP200-2")
      (footprint "FP-SF-1206FP-MFG")
      (description "FUSE BOARD MOUNT 2A 63VDC 1206")
      (libsource (lib "Altium Content Vault") (part "5bcf9b9f640e542cf0359d10258e979"))
    )
    (comp (ref "F18")
      (value "SF-1206FP200-2")
      (footprint "FP-SF-1206FP-MFG")
      (description "FUSE BOARD MOUNT 2A 63VDC 1206")
      (libsource (lib "Altium Content Vault") (part "5bcf9b9f640e542cf0359d10258e979"))
    )
    (comp (ref "F19")
      (value "SF-1206FP200-2")
      (footprint "FP-SF-1206FP-MFG")
      (description "FUSE BOARD MOUNT 2A 63VDC 1206")
      (libsource (lib "Altium Content Vault") (part "5bcf9b9f640e542cf0359d10258e979"))
    )
    (comp (ref "F21")
      (value "SF-1206FP200-2")
      (footprint "FP-SF-1206FP-MFG")
      (description "FUSE BOARD MOUNT 2A 63VDC 1206")
      (libsource (lib "Altium Content Vault") (part "5bcf9b9f640e542cf0359d10258e979"))
    )
    (comp (ref "F22")
      (value "SF-1206FP200-2")
      (footprint "FP-SF-1206FP-MFG")
      (description "FUSE BOARD MOUNT 2A 63VDC 1206")
      (libsource (lib "Altium Content Vault") (part "5bcf9b9f640e542cf0359d10258e979"))
    )
    (comp (ref "J1")
      (value "FM4-NZRP-PCB-1")
      (footprint "FM4-NZRP-PCB-1-Footprint-1")
      (description "Connector RF Mini-FAKRA Plug 9GHz 50Ohm Solder Right Angle Through Hole")
      (libsource (lib "Space Concordia") (part "CMP-002-00085-1"))
    )
    (comp (ref "J3")
      (value "776087-1")
      (footprint "FP-776087-1-MFG")
      (description "CONN HEADER R/A 23POS 4MM")
      (libsource (lib "Altium Content Vault") (part "1cdbe6524175775e54446a79a4f0ed8"))
    )
    (comp (ref "J4")
      (value "FM4-NZRP-PCB-1")
      (footprint "FM4-NZRP-PCB-1-Footprint-1")
      (description "Connector RF Mini-FAKRA Plug 9GHz 50Ohm Solder Right Angle Through Hole")
      (libsource (lib "Space Concordia") (part "CMP-002-00085-1"))
    )
    (comp (ref "J5")
      (value "47659-1100")
      (footprint "FP-47659-1100-MFG")
      (description "HDMI Connector, 19 Contact(s), Female, Straight, Surface Mount Terminal, Locking, Receptacle")
      (libsource (lib "Space Concordia") (part "47659-1100"))
    )
    (comp (ref "J6")
      (value "10118193-0001LF")
      (footprint "FCI-10118193-0001LF-5_V")
      (description "Micro USB B Type Receptacle, -55 to 85 degC, 5-Pin SMD, RoHS, Tape and Reel")
      (fields (field (name "MANUFACTURER") "FCI"))
      (libsource (lib "Altium Content Vault") (part "USB-5-6SHLD"))
    )
    (comp (ref "J7")
      (value "HTSW-104-07-G-S")
      (footprint "FP-HTSW-104-07-G-S-MFG")
      (description "CONN HEADER VERT 4POS 2.54MM")
      (libsource (lib "") (part "299a8cea1bdcbc3624fe62c390fa72c_1"))
    )
    (comp (ref "J8")
      (value "99S23F-40MA5-Z")
      (footprint "FP-99S23F-40MA5-Z-MFG")
      (description "HSD(M), R/A, 2GHz, 100Ohms, PCB, Solder, Thru-Hole, Tin, Gold, Keyed/Coded, Water Blue")
      (libsource (lib "Space Concordia") (part "99S23F-40MA5-Z"))
    )
    (comp (ref "J9")
      (value "47053-1000")
      (footprint "FP-470531000-MFG")
      (description "CONN HEADER VERT 4POS 2.54MM")
      (libsource (lib "Altium Content Vault") (part "299a8cea1bdcbc3624fe62c390fa72c"))
    )
    (comp (ref "J10")
      (value "5-2301995-4")
      (footprint "FP-5-2301995-4-MFG")
      (description "CONN JACK 1PORT 1000 BASE-T PCB")
      (libsource (lib "Altium Content Vault") (part "0805b62904d83b460e670db7b39b4f8"))
    )
    (comp (ref "J11")
      (value "47053-1000")
      (footprint "FP-470531000-MFG")
      (description "CONN HEADER VERT 4POS 2.54MM")
      (libsource (lib "Altium Content Vault") (part "299a8cea1bdcbc3624fe62c390fa72c"))
    )
    (comp (ref "MH1")
      (value "PTHV6")
      (footprint "PTHV6 M2")
      (libsource (lib "Space Concordia") (part "PTHV6"))
    )
    (comp (ref "MH2")
      (value "PTHV6")
      (footprint "PTHV6 M2")
      (libsource (lib "Space Concordia") (part "PTHV6"))
    )
    (comp (ref "MH3")
      (value "PTHV6")
      (footprint "PTHV6 M2")
      (libsource (lib "Space Concordia") (part "PTHV6"))
    )
    (comp (ref "MH4")
      (value "PTHV6")
      (footprint "PTHV6 M2")
      (libsource (lib "Space Concordia") (part "PTHV6"))
    )
    (comp (ref "MH5")
      (value "PTHV6")
      (footprint "PTHV6 M2")
      (libsource (lib "Space Concordia") (part "PTHV6"))
    )
    (comp (ref "MH6")
      (value "PTHV6")
      (footprint "PTHV6 M2")
      (libsource (lib "Space Concordia") (part "PTHV6"))
    )
    (comp (ref "MH7")
      (value "PTHV6")
      (footprint "PTHV6 M2")
      (libsource (lib "Space Concordia") (part "PTHV6"))
    )
    (comp (ref "MH8")
      (value "PTHV6")
      (footprint "PTHV6 M2")
      (libsource (lib "Space Concordia") (part "PTHV6"))
    )
    (comp (ref "MH9")
      (value "PTHV6")
      (footprint "PTHV6 M2")
      (libsource (lib "Space Concordia") (part "PTHV6"))
    )
    (comp (ref "MH10")
      (value "PTHV6")
      (footprint "PTHV6 M2")
      (libsource (lib "Space Concordia") (part "PTHV6"))
    )
    (comp (ref "MH11")
      (value "PTHV6")
      (footprint "PTHV6 M2")
      (libsource (lib "Space Concordia") (part "PTHV6"))
    )
    (comp (ref "MH12")
      (value "PTHV6")
      (footprint "PTHV6 M2")
      (libsource (lib "Space Concordia") (part "PTHV6"))
    )
    (comp (ref "Q23")
      (value "DMN2710UVQ-13")
      (footprint "SOTFL50P162X60-6N")
      (description "MOSFET Array, Dual N Channel, 20 V, 920 mA, 450 Milliohms, SOT-563, 6 Pins")
      (libsource (lib "Space Concordia") (part "DMN2710UVQ-13"))
    )
    (comp (ref "Q24")
      (value "DMN2710UVQ-13")
      (footprint "SOTFL50P162X60-6N")
      (description "MOSFET Array, Dual N Channel, 20 V, 920 mA, 450 Milliohms, SOT-563, 6 Pins")
      (libsource (lib "Space Concordia") (part "DMN2710UVQ-13"))
    )
    (comp (ref "Q25")
      (value "DMN2710UVQ-13")
      (footprint "SOTFL50P162X60-6N")
      (description "MOSFET Array, Dual N Channel, 20 V, 920 mA, 450 Milliohms, SOT-563, 6 Pins")
      (libsource (lib "Space Concordia") (part "DMN2710UVQ-13"))
    )
    (comp (ref "Q26")
      (value "BSS138W-7-F")
      (footprint "DIOD-SOT323-3_V")
      (fields (field (name "MANUFACTURER") "DiodesIncorporated"))
      (libsource (lib "Altium Content Vault") (part "NEMOS-GSD-3"))
    )
    (comp (ref "Q27")
      (value "DMN2710UVQ-13")
      (footprint "SOTFL50P162X60-6N")
      (description "MOSFET Array, Dual N Channel, 20 V, 920 mA, 450 Milliohms, SOT-563, 6 Pins")
      (libsource (lib "Space Concordia") (part "DMN2710UVQ-13"))
    )
    (comp (ref "Q28")
      (value "DMN2710UVQ-13")
      (footprint "SOTFL50P162X60-6N")
      (description "MOSFET Array, Dual N Channel, 20 V, 920 mA, 450 Milliohms, SOT-563, 6 Pins")
      (libsource (lib "Space Concordia") (part "DMN2710UVQ-13"))
    )
    (comp (ref "R138")
      (value "100k")
      (footprint "R0603B")
      (description "Resistor")
      (libsource (lib "Space Concordia") (part "Resistor"))
    )
    (comp (ref "R139")
      (value "100k")
      (footprint "R0603B")
      (description "Resistor")
      (libsource (lib "Space Concordia") (part "Resistor"))
    )
    (comp (ref "R140")
      (value "100k")
      (footprint "R0603B")
      (description "Resistor")
      (libsource (lib "Space Concordia") (part "Resistor"))
    )
    (comp (ref "R141")
      (value "100k")
      (footprint "R0603B")
      (description "Resistor")
      (libsource (lib "Space Concordia") (part "Resistor"))
    )
    (comp (ref "R142")
      (value "100k")
      (footprint "R0603B")
      (description "Resistor")
      (libsource (lib "Space Concordia") (part "Resistor"))
    )
    (comp (ref "R143")
      (value "10k")
      (footprint "R0603B")
      (description "Resistor")
      (libsource (lib "Space Concordia") (part "Resistor"))
    )
    (comp (ref "R144")
      (value "1M")
      (footprint "R0603B")
      (description "Resistor")
      (libsource (lib "Space Concordia") (part "Resistor"))
    )
    (comp (ref "R145")
      (value "1k")
      (footprint "R0603B")
      (description "Resistor")
      (libsource (lib "Space Concordia") (part "Resistor"))
    )
    (comp (ref "R146")
      (value "ERT-J1VR103J")
      (footprint "RESC1608X90X30ML15T20")
      (fields (field (name "MANUFACTURER") "Panasonic"))
      (libsource (lib "Altium Content Vault") (part "RES"))
    )
    (comp (ref "R147")
      (value "100k")
      (footprint "R0603B")
      (description "Resistor")
      (libsource (lib "Space Concordia") (part "Resistor"))
    )
    (comp (ref "R148")
      (value "100k")
      (footprint "R0603B")
      (description "Resistor")
      (libsource (lib "Space Concordia") (part "Resistor"))
    )
    (comp (ref "R149")
      (value "1k")
      (footprint "R0603B")
      (description "Resistor")
      (libsource (lib "Space Concordia") (part "Resistor"))
    )
    (comp (ref "R150")
      (value "100k")
      (footprint "R0603B")
      (description "Resistor")
      (libsource (lib "Space Concordia") (part "Resistor"))
    )
    (comp (ref "R151")
      (value "0402 JUMPER")
      (footprint "RESC1005X40X25ML05T05")
      (description "READ THE NAME")
      (libsource (lib "Space Concordia") (part "CMP-009-00206-2"))
    )
    (comp (ref "R152")
      (value "0402 JUMPER")
      (footprint "RESC1005X40X25ML05T05")
      (description "READ THE NAME")
      (libsource (lib "Space Concordia") (part "CMP-009-00206-2"))
    )
    (comp (ref "R153")
      (value "0402 JUMPER")
      (footprint "RESC1005X40X25ML05T05")
      (description "READ THE NAME")
      (libsource (lib "Space Concordia") (part "CMP-009-00206-2"))
    )
    (comp (ref "R154")
      (value "0402 JUMPER")
      (footprint "RESC1005X40X25ML05T05")
      (description "READ THE NAME")
      (libsource (lib "Space Concordia") (part "CMP-009-00206-2"))
    )
    (comp (ref "R155")
      (value "0402 JUMPER")
      (footprint "RESC1005X40X25ML05T05")
      (description "READ THE NAME")
      (libsource (lib "Space Concordia") (part "CMP-009-00206-2"))
    )
    (comp (ref "R156")
      (value "0402 JUMPER")
      (footprint "RESC1005X40X25ML05T05")
      (description "READ THE NAME")
      (libsource (lib "Space Concordia") (part "CMP-009-00206-2"))
    )
    (comp (ref "R157")
      (value "0402 JUMPER")
      (footprint "RESC1005X40X25ML05T05")
      (description "READ THE NAME")
      (libsource (lib "Space Concordia") (part "CMP-009-00206-2"))
    )
    (comp (ref "R158")
      (value "0402 JUMPER")
      (footprint "RESC1005X40X25ML05T05")
      (description "READ THE NAME")
      (libsource (lib "Space Concordia") (part "CMP-009-00206-2"))
    )
    (comp (ref "R164")
      (value "1k")
      (footprint "R0603B")
      (description "Resistor")
      (libsource (lib "Space Concordia") (part "Resistor"))
    )
    (comp (ref "R165")
      (value "100k")
      (footprint "R0603B")
      (description "Resistor")
      (libsource (lib "Space Concordia") (part "Resistor"))
    )
    (comp (ref "R166")
      (value "0402 JUMPER")
      (footprint "RESC1005X40X25ML05T05")
      (description "READ THE NAME")
      (libsource (lib "Space Concordia") (part "CMP-009-00206-2"))
    )
    (comp (ref "R167")
      (value "100k")
      (footprint "R0603B")
      (description "Resistor")
      (libsource (lib "Space Concordia") (part "Resistor"))
    )
    (comp (ref "R168")
      (value "100k")
      (footprint "R0603B")
      (description "Resistor")
      (fields (field (name "ALTIUM_VALUE") "100k"))
      (libsource (lib "Space Concordia") (part "Resistor"))
    )
    (comp (ref "R169")
      (value "100k")
      (footprint "R0603B")
      (description "Resistor")
      (fields (field (name "ALTIUM_VALUE") "100k"))
      (libsource (lib "Space Concordia") (part "Resistor"))
    )
    (comp (ref "R170")
      (value "100k")
      (footprint "R0603B")
      (description "Resistor")
      (fields (field (name "ALTIUM_VALUE") "100k"))
      (libsource (lib "Space Concordia") (part "Resistor"))
    )
    (comp (ref "R171")
      (value "100k")
      (footprint "R0603B")
      (description "Resistor")
      (fields (field (name "ALTIUM_VALUE") "100k"))
      (libsource (lib "Space Concordia") (part "Resistor"))
    )
    (comp (ref "R172")
      (value "1k")
      (footprint "R0603B")
      (description "Resistor")
      (libsource (lib "Space Concordia") (part "Resistor"))
    )
    (comp (ref "R173")
      (value "1k")
      (footprint "R0603B")
      (description "Resistor")
      (libsource (lib "Space Concordia") (part "Resistor"))
    )
    (comp (ref "R174")
      (value "1k")
      (footprint "R0603B")
      (description "Resistor")
      (libsource (lib "Space Concordia") (part "Resistor"))
    )
    (comp (ref "R175")
      (value "100k")
      (footprint "R0603B")
      (description "Resistor")
      (fields (field (name "ALTIUM_VALUE") "100k"))
      (libsource (lib "Space Concordia") (part "Resistor"))
    )
    (comp (ref "R176")
      (value "100k")
      (footprint "R0603B")
      (description "Resistor")
      (fields (field (name "ALTIUM_VALUE") "100k"))
      (libsource (lib "Space Concordia") (part "Resistor"))
    )
    (comp (ref "R177")
      (value "1k")
      (footprint "R0603B")
      (description "Resistor")
      (libsource (lib "Space Concordia") (part "Resistor"))
    )
    (comp (ref "R178")
      (value "1k")
      (footprint "R0603B")
      (description "Resistor")
      (libsource (lib "Space Concordia") (part "Resistor"))
    )
    (comp (ref "R179")
      (value "1k")
      (footprint "R0603B")
      (description "Resistor")
      (libsource (lib "Space Concordia") (part "Resistor"))
    )
    (comp (ref "R180")
      (value "100k")
      (footprint "R0603B")
      (description "Resistor")
      (fields (field (name "ALTIUM_VALUE") "100k"))
      (libsource (lib "Space Concordia") (part "Resistor"))
    )
    (comp (ref "R181")
      (value "100k")
      (footprint "R0603B")
      (description "Resistor")
      (fields (field (name "ALTIUM_VALUE") "100k"))
      (libsource (lib "Space Concordia") (part "Resistor"))
    )
    (comp (ref "R182")
      (value "100k")
      (footprint "R0603B")
      (description "Resistor")
      (libsource (lib "Space Concordia") (part "Resistor"))
    )
    (comp (ref "R183")
      (value "0402 JUMPER")
      (footprint "RESC1005X40X25ML05T05")
      (description "READ THE NAME")
      (libsource (lib "Space Concordia") (part "CMP-009-00206-2"))
    )
    (comp (ref "R184")
      (value "0402 JUMPER")
      (footprint "RESC1005X40X25ML05T05")
      (description "READ THE NAME")
      (libsource (lib "Space Concordia") (part "CMP-009-00206-2"))
    )
    (comp (ref "R269")
      (value "0402 JUMPER")
      (footprint "RESC1005X40X25ML05T05")
      (description "READ THE NAME")
      (libsource (lib "Space Concordia") (part "CMP-009-00206-2"))
    )
    (comp (ref "R270")
      (value "0402 JUMPER")
      (footprint "RESC1005X40X25ML05T05")
      (description "READ THE NAME")
      (libsource (lib "Space Concordia") (part "CMP-009-00206-2"))
    )
    (comp (ref "R271")
      (value "0402 JUMPER")
      (footprint "RESC1005X40X25ML05T05")
      (description "READ THE NAME")
      (libsource (lib "Space Concordia") (part "CMP-009-00206-2"))
    )
    (comp (ref "R272")
      (value "0402 JUMPER")
      (footprint "RESC1005X40X25ML05T05")
      (description "READ THE NAME")
      (libsource (lib "Space Concordia") (part "CMP-009-00206-2"))
    )
    (comp (ref "R273")
      (value "0402 JUMPER")
      (footprint "RESC1005X40X25ML05T05")
      (description "READ THE NAME")
      (libsource (lib "Space Concordia") (part "CMP-009-00206-2"))
    )
    (comp (ref "R274")
      (value "0402 JUMPER")
      (footprint "RESC1005X40X25ML05T05")
      (description "READ THE NAME")
      (libsource (lib "Space Concordia") (part "CMP-009-00206-2"))
    )
    (comp (ref "R275")
      (value "0402 JUMPER")
      (footprint "RESC1005X40X25ML05T05")
      (description "READ THE NAME")
      (libsource (lib "Space Concordia") (part "CMP-009-00206-2"))
    )
    (comp (ref "R276")
      (value "0402 JUMPER")
      (footprint "RESC1005X40X25ML05T05")
      (description "READ THE NAME")
      (libsource (lib "Space Concordia") (part "CMP-009-00206-2"))
    )
    (comp (ref "R277")
      (value "0402 JUMPER")
      (footprint "RESC1005X40X25ML05T05")
      (description "READ THE NAME")
      (libsource (lib "Space Concordia") (part "CMP-009-00206-2"))
    )
    (comp (ref "R278")
      (value "0402 JUMPER")
      (footprint "RESC1005X40X25ML05T05")
      (description "READ THE NAME")
      (libsource (lib "Space Concordia") (part "CMP-009-00206-2"))
    )
    (comp (ref "R279")
      (value "0402 JUMPER")
      (footprint "RESC1005X40X25ML05T05")
      (description "READ THE NAME")
      (libsource (lib "Space Concordia") (part "CMP-009-00206-2"))
    )
    (comp (ref "R280")
      (value "0402 JUMPER")
      (footprint "RESC1005X40X25ML05T05")
      (description "READ THE NAME")
      (libsource (lib "Space Concordia") (part "CMP-009-00206-2"))
    )
    (comp (ref "TP1")
      (value "TPAD6R")
      (footprint "New footprint 1")
      (description "Test Point .6mm")
      (libsource (lib "Space Concordia") (part "TP"))
    )
    (comp (ref "TP2")
      (value "TPAD6R")
      (footprint "New footprint 1")
      (description "Test Point .6mm")
      (libsource (lib "Space Concordia") (part "TP"))
    )
    (comp (ref "TP3")
      (value "TPAD6R")
      (footprint "New footprint 1")
      (description "Test Point .6mm")
      (libsource (lib "Space Concordia") (part "TP"))
    )
    (comp (ref "TP4")
      (value "TPAD6R")
      (footprint "New footprint 1")
      (description "Test Point .6mm")
      (libsource (lib "Space Concordia") (part "TP"))
    )
    (comp (ref "TP5")
      (value "TPAD6R")
      (footprint "New footprint 1")
      (description "Test Point .6mm")
      (libsource (lib "Space Concordia") (part "TP"))
    )
    (comp (ref "TP6")
      (value "TPAD6R")
      (footprint "New footprint 1")
      (description "Test Point .6mm")
      (libsource (lib "Space Concordia") (part "TP"))
    )
    (comp (ref "TP7")
      (value "TPAD6R")
      (footprint "New footprint 1")
      (description "Test Point .6mm")
      (libsource (lib "Space Concordia") (part "TP"))
    )
    (comp (ref "TP8")
      (value "TPAD6R")
      (footprint "New footprint 1")
      (description "Test Point .6mm")
      (libsource (lib "Space Concordia") (part "TP"))
    )
    (comp (ref "U15")
      (value "AP22804AW5-7")
      (footprint "SOT95P285X140-5N")
      (description "SINGLE CHANNEL POWER DISTRIBUTION LOAD SWITCH, -40 to 85°C pF, RoHS")
      (libsource (lib "Space Concordia") (part "AP22804AW5-7"))
    )
    (comp (ref "U16")
      (value "AP22804AW5-7")
      (footprint "SOT95P285X140-5N")
      (description "SINGLE CHANNEL POWER DISTRIBUTION LOAD SWITCH, -40 to 85°C pF, RoHS")
      (libsource (lib "Space Concordia") (part "AP22804AW5-7"))
    )
    (comp (ref "U17")
      (value "AP22804AW5-7")
      (footprint "SOT95P285X140-5N")
      (description "SINGLE CHANNEL POWER DISTRIBUTION LOAD SWITCH, -40 to 85°C pF, RoHS")
      (libsource (lib "") (part "AP22804AW5-7_1"))
    )
    (comp (ref "U18")
      (value "NC7SZ125M5X")
      (footprint "FAIR-SOT23-5_V")
      (fields (field (name "MANUFACTURER") "Fairchild Semiconductor"))
      (libsource (lib "Altium Content Vault") (part "FAIR-NC7SZ125-SOT23-5"))
    )
    (comp (ref "U19")
      (value "AP22804AW5-7")
      (footprint "SOT95P285X140-5N")
      (description "SINGLE CHANNEL POWER DISTRIBUTION LOAD SWITCH, -40 to 85°C pF, RoHS")
      (libsource (lib "Space Concordia") (part "AP22804AW5-7"))
    )
    (comp (ref "U20")
      (value "DNP/NC7SZ125M5X")
      (footprint "FAIR-SOT23-5_V")
      (fields (field (name "MANUFACTURER") "Fairchild Semiconductor"))
      (libsource (lib "Altium Content Vault") (part "FAIR-NC7SZ125-SOT23-5"))
    )
  )
  (nets
    (net (code "7") (name "/1V8_CPU_FAN_PWM") (class "Default")
      (node (ref "R178") (pin "2") (pinfunction "2_2") (pintype "passive"))
    )
    (net (code "8") (name "/1V8_CPU_FAN_TACH") (class "Default")
      (node (ref "R172") (pin "2") (pinfunction "2_2") (pintype "passive"))
    )
    (net (code "12") (name "/1V8_GPIO01") (class "Default")
      (node (ref "TP3") (pin "1") (pinfunction "TP_1") (pintype "passive"))
    )
    (net (code "13") (name "/1V8_GPIO04") (class "Default")
      (node (ref "TP4") (pin "1") (pinfunction "TP_1") (pintype "passive"))
    )
    (net (code "14") (name "/1V8_GPIO06") (class "Default")
      (node (ref "TP5") (pin "1") (pinfunction "TP_1") (pintype "passive"))
    )
    (net (code "15") (name "/1V8_GPIO07_PWM") (class "Default")
      (node (ref "R173") (pin "2") (pinfunction "2_2") (pintype "passive"))
    )
    (net (code "16") (name "/1V8_GPIO09") (class "Default")
      (node (ref "TP6") (pin "1") (pinfunction "TP_1") (pintype "passive"))
    )
    (net (code "17") (name "/1V8_GPIO11") (class "Default")
      (node (ref "TP7") (pin "1") (pinfunction "TP_1") (pintype "passive"))
    )
    (net (code "18") (name "/1V8_GPIO12") (class "Default")
      (node (ref "TP8") (pin "1") (pinfunction "TP_1") (pintype "passive"))
    )
    (net (code "19") (name "/1V8_GPIO13_PWM") (class "Default")
      (node (ref "R179") (pin "2") (pinfunction "2_2") (pintype "passive"))
    )
    (net (code "36") (name "/1V8_nM2_ALERT") (class "Default")
      (node (ref "U20") (pin "4") (pinfunction "Y_4") (pintype "tri_state"))
    )
    (net (code "39") (name "/1V8_nSYS_RESET") (class "Default")
      (node (ref "R143") (pin "1") (pinfunction "1_1") (pintype "passive"))
      (node (ref "R144") (pin "2") (pinfunction "2_2") (pintype "passive"))
      (node (ref "U17") (pin "4") (pinfunction "EN_4") (pintype "input"))
    )
    (net (code "40") (name "/1V8_nUSB0_VBUS_DET") (class "Default")
      (node (ref "R166") (pin "2") (pinfunction "2_2") (pintype "passive"))
    )
    (net (code "73") (name "/3V3_HPD") (class "Default")
      (node (ref "R280") (pin "2") (pinfunction "2_2") (pintype "passive"))
    )
    (net (code "76") (name "/3V3_I2C1_SCL") (class "Default")
      (node (ref "TP2") (pin "1") (pinfunction "TP_1") (pintype "passive"))
    )
    (net (code "77") (name "/3V3_I2C1_SDA") (class "Default")
      (node (ref "TP1") (pin "1") (pinfunction "TP_1") (pintype "passive"))
    )
    (net (code "106") (name "/3V3_MODULE_ID") (class "Default")
      (node (ref "U18") (pin "2") (pinfunction "A_2") (pintype "input"))
    )
    (net (code "118") (name "/3V3_UART2_RXD") (class "Default")
      (node (ref "J7") (pin "4") (pinfunction "4_4") (pintype "passive"))
    )
    (net (code "119") (name "/3V3_UART2_TXD") (class "Default")
      (node (ref "J7") (pin "3") (pinfunction "3_3") (pintype "passive"))
    )
    (net (code "120") (name "/3V3_USB_PWR_EN") (class "Default")
      (node (ref "U19") (pin "4") (pinfunction "EN_4") (pintype "input"))
    )
    (net (code "125") (name "/3V3_nSYS_RESET") (class "Default")
      (node (ref "R149") (pin "2") (pinfunction "2_2") (pintype "passive"))
      (node (ref "U17") (pin "1") (pinfunction "VOUT_1") (pintype "power_in"))
    )
    (net (code "127") (name "/5V0_DBG_USB_VBUS") (class "Default")
      (node (ref "C156") (pin "1") (pinfunction "1_1") (pintype "passive"))
      (node (ref "D23") (pin "4") (pinfunction "IO3_4") (pintype "bidirectional"))
      (node (ref "J6") (pin "1") (pinfunction "VBUS_1") (pintype "passive"))
      (node (ref "Q26") (pin "1") (pinfunction "G_1") (pintype "passive"))
      (node (ref "R167") (pin "2") (pinfunction "2_2") (pintype "passive"))
    )
    (net (code "129") (name "/5V0_POWER_EN") (class "Default")
      (node (ref "R138") (pin "2") (pinfunction "2_2") (pintype "passive"))
      (node (ref "U15") (pin "1") (pinfunction "VOUT_1") (pintype "power_in"))
    )
    (net (code "130") (name "/5V0_SLEEP{slash}nWAKE") (class "Default")
      (node (ref "R140") (pin "2") (pinfunction "2_2") (pintype "passive"))
      (node (ref "U16") (pin "1") (pinfunction "VOUT_1") (pintype "power_in"))
    )
    (net (code "131") (name "/5V0_nSHDN_REQ") (class "Default")
      (node (ref "D14") (pin "1") (pinfunction "C_1") (pintype "passive"))
    )
    (net (code "136") (name "/AMBIENT_TEMP") (class "Default")
      (node (ref "R145") (pin "1") (pinfunction "1_1") (pintype "passive"))
      (node (ref "R146") (pin "2") (pinfunction "2_2") (pintype "passive"))
    )
    (net (code "137") (name "/CAN_N") (class "Default")
      (node (ref "J3") (pin "23") (pinfunction "23_23") (pintype "passive"))
    )
    (net (code "138") (name "/CAN_P") (class "Default")
      (node (ref "J3") (pin "22") (pinfunction "22_22") (pintype "passive"))
    )
    (net (code "159") (name "/DDC_SCK") (class "Default")
      (node (ref "R278") (pin "2") (pinfunction "2_2") (pintype "passive"))
    )
    (net (code "160") (name "/DDC_SDA") (class "Default")
      (node (ref "R277") (pin "2") (pinfunction "2_2") (pintype "passive"))
    )
    (net (code "169") (name "/ETH_MDI0_N") (class "Default")
      (node (ref "D27") (pin "2") (pinfunction "IO2_2") (pintype "bidirectional"))
      (node (ref "J10") (pin "P2") (pinfunction "P2_P2") (pintype "passive"))
    )
    (net (code "170") (name "/ETH_MDI0_P") (class "Default")
      (node (ref "D27") (pin "1") (pinfunction "IO1_1") (pintype "bidirectional"))
      (node (ref "J10") (pin "P1") (pinfunction "P1_P1") (pintype "passive"))
    )
    (net (code "171") (name "/ETH_MDI1_N") (class "Default")
      (node (ref "D27") (pin "5") (pinfunction "IO4_5") (pintype "bidirectional"))
      (node (ref "J10") (pin "P4") (pinfunction "P4_P4") (pintype "passive"))
    )
    (net (code "172") (name "/ETH_MDI1_P") (class "Default")
      (node (ref "D27") (pin "4") (pinfunction "IO3_4") (pintype "bidirectional"))
      (node (ref "J10") (pin "P3") (pinfunction "P3_P3") (pintype "passive"))
    )
    (net (code "173") (name "/ETH_MDI2_N") (class "Default")
      (node (ref "D28") (pin "2") (pinfunction "IO2_2") (pintype "bidirectional"))
      (node (ref "J10") (pin "P8") (pinfunction "P8_P8") (pintype "passive"))
    )
    (net (code "174") (name "/ETH_MDI2_P") (class "Default")
      (node (ref "D28") (pin "1") (pinfunction "IO1_1") (pintype "bidirectional"))
      (node (ref "J10") (pin "P7") (pinfunction "P7_P7") (pintype "passive"))
    )
    (net (code "175") (name "/ETH_MDI3_N") (class "Default")
      (node (ref "D28") (pin "5") (pinfunction "IO4_5") (pintype "bidirectional"))
      (node (ref "J10") (pin "P10") (pinfunction "P10_P10") (pintype "passive"))
    )
    (net (code "176") (name "/ETH_MDI3_P") (class "Default")
      (node (ref "D28") (pin "4") (pinfunction "IO3_4") (pintype "bidirectional"))
      (node (ref "J10") (pin "P9") (pinfunction "P9_P9") (pintype "passive"))
    )
    (net (code "177") (name "/ETH_USB_5V") (class "Default")
      (node (ref "D29") (pin "1") (pinfunction "IO1_1") (pintype "bidirectional"))
      (node (ref "U19") (pin "1") (pinfunction "VOUT_1") (pintype "power_in"))
    )
    (net (code "178") (name "/FAN_0_PWM") (class "Default")
      (node (ref "J9") (pin "4") (pinfunction "4_4") (pintype "passive"))
      (node (ref "Q27") (pin "3") (pinfunction "Drain2_3") (pintype "passive"))
      (node (ref "R175") (pin "1") (pinfunction "1_1") (pintype "passive"))
    )
    (net (code "179") (name "/FAN_0_TACH") (class "Default")
      (node (ref "J9") (pin "3") (pinfunction "3_3") (pintype "passive"))
      (node (ref "Q27") (pin "6") (pinfunction "Drain1_6") (pintype "passive"))
      (node (ref "R168") (pin "1") (pinfunction "1_1") (pintype "passive"))
    )
    (net (code "180") (name "/FAN_1_PWM") (class "Default")
      (node (ref "J11") (pin "4") (pinfunction "4_4") (pintype "passive"))
      (node (ref "Q28") (pin "3") (pinfunction "Drain2_3") (pintype "passive"))
      (node (ref "R176") (pin "1") (pinfunction "1_1") (pintype "passive"))
    )
    (net (code "181") (name "/FAN_1_TACH") (class "Default")
      (node (ref "J11") (pin "3") (pinfunction "3_3") (pintype "passive"))
      (node (ref "Q28") (pin "6") (pinfunction "Drain1_6") (pintype "passive"))
      (node (ref "R169") (pin "1") (pinfunction "1_1") (pintype "passive"))
    )
    (net (code "182") (name "/HDMI_5V") (class "Default")
      (node (ref "D21") (pin "2") (pinfunction "IO2_2") (pintype "bidirectional"))
      (node (ref "D21") (pin "9") (pinfunction "NC_9") (pintype "passive"))
      (node (ref "J5") (pin "18") (pinfunction "5V_18") (pintype "power_in"))
      (node (ref "R279") (pin "1") (pinfunction "1_1") (pintype "passive"))
    )
    (net (code "183") (name "/HDMI_5V_1") (class "Default")
      (node (ref "R279") (pin "2") (pinfunction "2_2") (pintype "passive"))
    )
    (net (code "184") (name "/HDMI_CEC") (class "Default")
      (node (ref "J5") (pin "13") (pinfunction "CEC_13") (pintype "bidirectional"))
    )
    (net (code "185") (name "/HDMI_CLK_N") (class "Default")
      (node (ref "R158") (pin "1") (pinfunction "1_1") (pintype "passive"))
      (node (ref "R276") (pin "1") (pinfunction "1_1") (pintype "passive"))
    )
    (net (code "186") (name "/HDMI_CLK_P") (class "Default")
      (node (ref "R157") (pin "1") (pinfunction "1_1") (pintype "passive"))
      (node (ref "R275") (pin "1") (pinfunction "1_1") (pintype "passive"))
    )
    (net (code "187") (name "/HDMI_D0_N") (class "Default")
      (node (ref "R156") (pin "1") (pinfunction "1_1") (pintype "passive"))
      (node (ref "R270") (pin "1") (pinfunction "1_1") (pintype "passive"))
    )
    (net (code "188") (name "/HDMI_D0_P") (class "Default")
      (node (ref "R155") (pin "1") (pinfunction "1_1") (pintype "passive"))
      (node (ref "R269") (pin "1") (pinfunction "1_1") (pintype "passive"))
    )
    (net (code "189") (name "/HDMI_D1_N") (class "Default")
      (node (ref "R154") (pin "1") (pinfunction "1_1") (pintype "passive"))
      (node (ref "R272") (pin "1") (pinfunction "1_1") (pintype "passive"))
    )
    (net (code "190") (name "/HDMI_D1_P") (class "Default")
      (node (ref "R153") (pin "1") (pinfunction "1_1") (pintype "passive"))
      (node (ref "R271") (pin "1") (pinfunction "1_1") (pintype "passive"))
    )
    (net (code "191") (name "/HDMI_D2_N") (class "Default")
      (node (ref "R152") (pin "1") (pinfunction "1_1") (pintype "passive"))
      (node (ref "R274") (pin "1") (pinfunction "1_1") (pintype "passive"))
    )
    (net (code "192") (name "/HDMI_D2_P") (class "Default")
      (node (ref "R151") (pin "1") (pinfunction "1_1") (pintype "passive"))
      (node (ref "R273") (pin "1") (pinfunction "1_1") (pintype "passive"))
    )
    (net (code "193") (name "/HDMI_HP_DET") (class "Default")
      (node (ref "D21") (pin "1") (pinfunction "IO1_1") (pintype "bidirectional"))
      (node (ref "D21") (pin "10") (pinfunction "NC_10") (pintype "passive"))
      (node (ref "J5") (pin "19") (pinfunction "HOTPLUG_19") (pintype "output"))
      (node (ref "R280") (pin "1") (pinfunction "1_1") (pintype "passive"))
    )
    (net (code "194") (name "/HDMI_SCL") (class "Default")
      (node (ref "D21") (pin "5") (pinfunction "IO4_5") (pintype "bidirectional"))
      (node (ref "D21") (pin "6") (pinfunction "NC_6") (pintype "passive"))
      (node (ref "J5") (pin "15") (pinfunction "SCL_15") (pintype "input"))
      (node (ref "R278") (pin "1") (pinfunction "1_1") (pintype "passive"))
    )
    (net (code "195") (name "/HDMI_SDA") (class "Default")
      (node (ref "D21") (pin "4") (pinfunction "IO3_4") (pintype "bidirectional"))
      (node (ref "D21") (pin "7") (pinfunction "NC_7") (pintype "passive"))
      (node (ref "J5") (pin "16") (pinfunction "SDA_16") (pintype "bidirectional"))
      (node (ref "R277") (pin "1") (pinfunction "1_1") (pintype "passive"))
    )
    (net (code "197") (name "/HV_SYS_RESET") (class "Default")
      (node (ref "Q24") (pin "2") (pinfunction "Gate1_2") (pintype "passive"))
      (node (ref "Q24") (pin "5") (pinfunction "Gate2_5") (pintype "passive"))
      (node (ref "Q25") (pin "5") (pinfunction "Gate2_5") (pintype "passive"))
      (node (ref "Q25") (pin "6") (pinfunction "Drain1_6") (pintype "passive"))
      (node (ref "R148") (pin "1") (pinfunction "1_1") (pintype "passive"))
    )
    (net (code "198") (name "/IN_CK_N") (class "Default")
      (node (ref "R276") (pin "2") (pinfunction "2_2") (pintype "passive"))
    )
    (net (code "199") (name "/IN_CK_P") (class "Default")
      (node (ref "R275") (pin "2") (pinfunction "2_2") (pintype "passive"))
    )
    (net (code "200") (name "/IN_D0_N") (class "Default")
      (node (ref "R270") (pin "2") (pinfunction "2_2") (pintype "passive"))
    )
    (net (code "201") (name "/IN_D0_P") (class "Default")
      (node (ref "R269") (pin "2") (pinfunction "2_2") (pintype "passive"))
    )
    (net (code "202") (name "/IN_D1_N") (class "Default")
      (node (ref "R272") (pin "2") (pinfunction "2_2") (pintype "passive"))
    )
    (net (code "203") (name "/IN_D1_P") (class "Default")
      (node (ref "R271") (pin "2") (pinfunction "2_2") (pintype "passive"))
    )
    (net (code "204") (name "/IN_D2_N") (class "Default")
      (node (ref "R274") (pin "2") (pinfunction "2_2") (pintype "passive"))
    )
    (net (code "205") (name "/IN_D2_P") (class "Default")
      (node (ref "R273") (pin "2") (pinfunction "2_2") (pintype "passive"))
    )
    (net (code "206") (name "/OD_ETH_LED_ACT") (class "Default")
      (node (ref "J10") (pin "P13") (pinfunction "2_ANODE_GREEN/2_CATHODE_YELLOW_P13") (pintype "passive"))
    )
    (net (code "207") (name "/OD_ETH_LED_LINK") (class "Default")
      (node (ref "J10") (pin "P12") (pinfunction "1_CATHODE_GREEN/1_ANODE_YELLOW_P12") (pintype "passive"))
    )
    (net (code "216") (name "/P1_5V") (class "Default")
      (node (ref "D29") (pin "5") (pinfunction "IO4_5") (pintype "bidirectional"))
    )
    (net (code "217") (name "/P1_CK_N") (class "Default")
      (node (ref "D20") (pin "1") (pinfunction "IO1_1") (pintype "bidirectional"))
      (node (ref "D20") (pin "10") (pinfunction "NC_10") (pintype "passive"))
      (node (ref "J5") (pin "12") (pinfunction "CK_N_12") (pintype "input"))
      (node (ref "R158") (pin "2") (pinfunction "2_2") (pintype "passive"))
    )
    (net (code "218") (name "/P1_CK_P") (class "Default")
      (node (ref "D20") (pin "2") (pinfunction "IO2_2") (pintype "bidirectional"))
      (node (ref "D20") (pin "9") (pinfunction "NC_9") (pintype "passive"))
      (node (ref "J5") (pin "10") (pinfunction "CK_P_10") (pintype "input"))
      (node (ref "R157") (pin "2") (pinfunction "2_2") (pintype "passive"))
    )
    (net (code "219") (name "/P1_D0_N") (class "Default")
      (node (ref "D20") (pin "4") (pinfunction "IO3_4") (pintype "bidirectional"))
      (node (ref "D20") (pin "7") (pinfunction "NC_7") (pintype "passive"))
      (node (ref "J5") (pin "9") (pinfunction "D0_N_9") (pintype "input"))
      (node (ref "R156") (pin "2") (pinfunction "2_2") (pintype "passive"))
    )
    (net (code "220") (name "/P1_D0_P") (class "Default")
      (node (ref "D20") (pin "5") (pinfunction "IO4_5") (pintype "bidirectional"))
      (node (ref "D20") (pin "6") (pinfunction "NC_6") (pintype "passive"))
      (node (ref "J5") (pin "7") (pinfunction "D0_P_7") (pintype "input"))
      (node (ref "R155") (pin "2") (pinfunction "2_2") (pintype "passive"))
    )
    (net (code "221") (name "/P1_D1_N") (class "Default")
      (node (ref "D19") (pin "1") (pinfunction "IO1_1") (pintype "bidirectional"))
      (node (ref "D19") (pin "10") (pinfunction "NC_10") (pintype "passive"))
      (node (ref "J5") (pin "6") (pinfunction "D1_N_6") (pintype "input"))
      (node (ref "R154") (pin "2") (pinfunction "2_2") (pintype "passive"))
    )
    (net (code "222") (name "/P1_D1_P") (class "Default")
      (node (ref "D19") (pin "2") (pinfunction "IO2_2") (pintype "bidirectional"))
      (node (ref "D19") (pin "9") (pinfunction "NC_9") (pintype "passive"))
      (node (ref "J5") (pin "4") (pinfunction "D1_P_4") (pintype "input"))
      (node (ref "R153") (pin "2") (pinfunction "2_2") (pintype "passive"))
    )
    (net (code "223") (name "/P1_D2_N") (class "Default")
      (node (ref "D19") (pin "4") (pinfunction "IO3_4") (pintype "bidirectional"))
      (node (ref "D19") (pin "7") (pinfunction "NC_7") (pintype "passive"))
      (node (ref "J5") (pin "3") (pinfunction "D2_N_3") (pintype "input"))
      (node (ref "R152") (pin "2") (pinfunction "2_2") (pintype "passive"))
    )
    (net (code "224") (name "/P1_D2_P") (class "Default")
      (node (ref "D19") (pin "5") (pinfunction "IO4_5") (pintype "bidirectional"))
      (node (ref "D19") (pin "6") (pinfunction "NC_6") (pintype "passive"))
      (node (ref "J5") (pin "1") (pinfunction "D2_P_1") (pintype "input"))
      (node (ref "R151") (pin "2") (pinfunction "2_2") (pintype "passive"))
    )
    (net (code "247") (name "/RF_MAX96724_0_SIO_A") (class "Default")
      (node (ref "J1") (pin "2") (pinfunction "2_2") (pintype "passive"))
    )
    (net (code "248") (name "/RF_MAX96724_0_SIO_B") (class "Default")
      (node (ref "J1") (pin "1") (pinfunction "1_1") (pintype "passive"))
    )
    (net (code "249") (name "/RF_MAX96724_0_SIO_C") (class "Default")
      (node (ref "J1") (pin "4") (pinfunction "4_4") (pintype "passive"))
    )
    (net (code "250") (name "/RF_MAX96724_0_SIO_D") (class "Default")
      (node (ref "J1") (pin "3") (pinfunction "3_3") (pintype "passive"))
    )
    (net (code "251") (name "/RF_MAX96724_1_SIO_A") (class "Default")
      (node (ref "J4") (pin "2") (pinfunction "2_2") (pintype "passive"))
    )
    (net (code "252") (name "/RF_MAX96724_1_SIO_B") (class "Default")
      (node (ref "J4") (pin "1") (pinfunction "1_1") (pintype "passive"))
    )
    (net (code "253") (name "/RF_MAX96724_1_SIO_C") (class "Default")
      (node (ref "J4") (pin "4") (pinfunction "4_4") (pintype "passive"))
    )
    (net (code "254") (name "/RF_MAX96724_1_SIO_D") (class "Default")
      (node (ref "J4") (pin "3") (pinfunction "3_3") (pintype "passive"))
    )
    (net (code "255") (name "/RF_MAX96751_0_A_N") (class "Default")
      (node (ref "J8") (pin "3") (pinfunction "3_3") (pintype "passive"))
    )
    (net (code "256") (name "/RF_MAX96751_0_A_P") (class "Default")
      (node (ref "J8") (pin "1") (pinfunction "1_1") (pintype "passive"))
    )
    (net (code "257") (name "/RF_MAX96751_0_B_N") (class "Default")
      (node (ref "J8") (pin "2") (pinfunction "2_2") (pintype "passive"))
    )
    (net (code "258") (name "/RF_MAX96751_0_B_P") (class "Default")
      (node (ref "J8") (pin "4") (pinfunction "4_4") (pintype "passive"))
    )
    (net (code "259") (name "/RJ45_CT_CAP") (class "Default")
      (node (ref "C5") (pin "1") (pinfunction "1_1") (pintype "passive"))
      (node (ref "J10") (pin "P5") (pinfunction "P5_P5") (pintype "passive"))
      (node (ref "J10") (pin "P6") (pinfunction "P6_P6") (pintype "passive"))
    )
    (net (code "260") (name "/USB2_0_N") (class "Default")
      (node (ref "D23") (pin "2") (pinfunction "IO2_2") (pintype "bidirectional"))
      (node (ref "J6") (pin "2") (pinfunction "D-_2") (pintype "passive"))
    )
    (net (code "261") (name "/USB2_0_P") (class "Default")
      (node (ref "D23") (pin "1") (pinfunction "IO1_1") (pintype "bidirectional"))
      (node (ref "J6") (pin "3") (pinfunction "D+_3") (pintype "passive"))
    )
    (net (code "262") (name "/USB2_1_N") (class "Default")
      (node (ref "D29") (pin "2") (pinfunction "IO2_2") (pintype "bidirectional"))
    )
    (net (code "263") (name "/USB2_1_P") (class "Default")
      (node (ref "D29") (pin "4") (pinfunction "IO3_4") (pintype "bidirectional"))
    )
    (net (code "272") (name "/nNVME_M2_ALERT") (class "Default")
      (node (ref "R184") (pin "2") (pinfunction "2_2") (pintype "passive"))
    )
    (net (code "273") (name "/nWIFI_M2_ALERT") (class "Default")
      (node (ref "R183") (pin "2") (pinfunction "2_2") (pintype "passive"))
    )
    (net (code "274") (name "3V3_DES_0") (class "Default")
      (node (ref "F16") (pin "2") (pinfunction "2_2") (pintype "passive"))
    )
    (net (code "275") (name "3V3_DES_1") (class "Default")
      (node (ref "F17") (pin "2") (pinfunction "2_2") (pintype "passive"))
    )
    (net (code "276") (name "3V3_HDMI") (class "Default")
      (node (ref "F19") (pin "2") (pinfunction "2_2") (pintype "passive"))
    )
    (net (code "277") (name "3V3_INT") (class "Default")
      (node (ref "R142") (pin "2") (pinfunction "2_2") (pintype "passive"))
      (node (ref "R145") (pin "2") (pinfunction "2_2") (pintype "passive"))
      (node (ref "R147") (pin "2") (pinfunction "2_2") (pintype "passive"))
      (node (ref "U17") (pin "5") (pinfunction "VIN_5") (pintype "power_in"))
      (node (ref "U18") (pin "5") (pinfunction "VCC_5") (pintype "power_in"))
    )
    (net (code "278") (name "3V3_M2_NVME") (class "Default")
      (node (ref "F14") (pin "2") (pinfunction "2_2") (pintype "passive"))
    )
    (net (code "279") (name "3V3_M2_WIFI") (class "Default")
      (node (ref "F15") (pin "2") (pinfunction "2_2") (pintype "passive"))
    )
    (net (code "280") (name "3V3_MAIN") (class "Default")
      (node (ref "F14") (pin "1") (pinfunction "1_1") (pintype "passive"))
      (node (ref "F15") (pin "1") (pinfunction "1_1") (pintype "passive"))
      (node (ref "F16") (pin "1") (pinfunction "1_1") (pintype "passive"))
      (node (ref "F17") (pin "1") (pinfunction "1_1") (pintype "passive"))
      (node (ref "F18") (pin "1") (pinfunction "1_1") (pintype "passive"))
      (node (ref "F19") (pin "1") (pinfunction "1_1") (pintype "passive"))
      (node (ref "R164") (pin "1") (pinfunction "1_1") (pintype "passive"))
      (node (ref "R174") (pin "2") (pinfunction "2_2") (pintype "passive"))
      (node (ref "R177") (pin "2") (pinfunction "2_2") (pintype "passive"))
    )
    (net (code "281") (name "3V3_SER_0") (class "Default")
      (node (ref "F18") (pin "2") (pinfunction "2_2") (pintype "passive"))
    )
    (net (code "282") (name "5V0_HDMI") (class "Default")
      (node (ref "F11") (pin "2") (pinfunction "2_2") (pintype "passive"))
    )
    (net (code "284") (name "5V0_JETSON") (class "Default")
      (node (ref "F10") (pin "2") (pinfunction "2_2") (pintype "passive"))
      (node (ref "U15") (pin "5") (pinfunction "VIN_5") (pintype "power_in"))
      (node (ref "U16") (pin "5") (pinfunction "VIN_5") (pintype "power_in"))
    )
    (net (code "285") (name "5V0_MAIN") (class "Default")
      (node (ref "F10") (pin "1") (pinfunction "1_1") (pintype "passive"))
      (node (ref "F11") (pin "1") (pinfunction "1_1") (pintype "passive"))
      (node (ref "F12") (pin "1") (pinfunction "1_1") (pintype "passive"))
      (node (ref "F21") (pin "1") (pinfunction "1_1") (pintype "passive"))
      (node (ref "F22") (pin "1") (pinfunction "1_1") (pintype "passive"))
      (node (ref "R168") (pin "2") (pinfunction "2_2") (pintype "passive"))
      (node (ref "R169") (pin "2") (pinfunction "2_2") (pintype "passive"))
      (node (ref "R175") (pin "2") (pinfunction "2_2") (pintype "passive"))
      (node (ref "R176") (pin "2") (pinfunction "2_2") (pintype "passive"))
    )
    (net (code "286") (name "5V0_USB") (class "Default")
      (node (ref "F12") (pin "2") (pinfunction "2_2") (pintype "passive"))
      (node (ref "U19") (pin "5") (pinfunction "VIN_5") (pintype "power_in"))
    )
    (net (code "287") (name "12V0_JETSON") (class "Default")
      (node (ref "F9") (pin "2") (pinfunction "2_2") (pintype "passive"))
    )
    (net (code "288") (name "12V0_MAIN") (class "Default")
      (node (ref "F6") (pin "1") (pinfunction "1_1") (pintype "passive"))
      (node (ref "F7") (pin "1") (pinfunction "1_1") (pintype "passive"))
      (node (ref "F8") (pin "1") (pinfunction "1_1") (pintype "passive"))
      (node (ref "F9") (pin "1") (pinfunction "1_1") (pintype "passive"))
    )
    (net (code "289") (name "12V0_PoC_0") (class "Default")
      (node (ref "F6") (pin "2") (pinfunction "2_2") (pintype "passive"))
    )
    (net (code "290") (name "12V0_PoC_1") (class "Default")
      (node (ref "F7") (pin "2") (pinfunction "2_2") (pintype "passive"))
    )
    (net (code "291") (name "12V0_PoC_2") (class "Default")
      (node (ref "F8") (pin "2") (pinfunction "2_2") (pintype "passive"))
      (node (ref "J8") (pin "12") (pinfunction "12_12") (pintype "passive"))
    )
    (net (code "292") (name "APM_VCC") (class "Default")
      (node (ref "J3") (pin "12") (pinfunction "12_12") (pintype "passive"))
      (node (ref "J3") (pin "13") (pinfunction "13_13") (pintype "passive"))
      (node (ref "J3") (pin "19") (pinfunction "19_19") (pintype "passive"))
      (node (ref "J3") (pin "20") (pinfunction "20_20") (pintype "passive"))
      (node (ref "J3") (pin "4") (pinfunction "4_4") (pintype "passive"))
      (node (ref "J3") (pin "5") (pinfunction "5_5") (pintype "passive"))
    )
    (net (code "293") (name "CAR_VCC") (class "Default")
      (node (ref "J3") (pin "1") (pinfunction "1_1") (pintype "passive"))
      (node (ref "J3") (pin "10") (pinfunction "10_10") (pintype "passive"))
      (node (ref "J3") (pin "16") (pinfunction "16_16") (pintype "passive"))
      (node (ref "J3") (pin "17") (pinfunction "17_17") (pintype "passive"))
      (node (ref "J3") (pin "2") (pinfunction "2_2") (pintype "passive"))
      (node (ref "J3") (pin "9") (pinfunction "9_9") (pintype "passive"))
    )
    (net (code "294") (name "ETH_GND") (class "Default")
      (node (ref "C158") (pin "2") (pinfunction "2_2") (pintype "passive"))
      (node (ref "C159") (pin "2") (pinfunction "2_2") (pintype "passive"))
      (node (ref "C160") (pin "2") (pinfunction "2_2") (pintype "passive"))
      (node (ref "C161") (pin "2") (pinfunction "2_2") (pintype "passive"))
      (node (ref "C162") (pin "2") (pinfunction "2_2") (pintype "passive"))
      (node (ref "C163") (pin "2") (pinfunction "2_2") (pintype "passive"))
      (node (ref "C165") (pin "2") (pinfunction "2_2") (pintype "passive"))
      (node (ref "C166") (pin "2") (pinfunction "2_2") (pintype "passive"))
      (node (ref "C5") (pin "2") (pinfunction "2_2") (pintype "passive"))
      (node (ref "J10") (pin "1") (pinfunction "MNT_1_1") (pintype "passive"))
      (node (ref "J10") (pin "2") (pinfunction "MNT_2_2") (pintype "passive"))
    )
    (net (code "295") (name "GND") (class "Default")
      (node (ref "C156") (pin "2") (pinfunction "2_2") (pintype "passive"))
      (node (ref "C158") (pin "1") (pinfunction "1_1") (pintype "passive"))
      (node (ref "C159") (pin "1") (pinfunction "1_1") (pintype "passive"))
      (node (ref "C160") (pin "1") (pinfunction "1_1") (pintype "passive"))
      (node (ref "C161") (pin "1") (pinfunction "1_1") (pintype "passive"))
      (node (ref "C162") (pin "1") (pinfunction "1_1") (pintype "passive"))
      (node (ref "C163") (pin "1") (pinfunction "1_1") (pintype "passive"))
      (node (ref "C164") (pin "2") (pinfunction "2_2") (pintype "passive"))
      (node (ref "C165") (pin "1") (pinfunction "1_1") (pintype "passive"))
      (node (ref "C166") (pin "1") (pinfunction "1_1") (pintype "passive"))
      (node (ref "D15") (pin "3") (pinfunction "GND_3") (pintype "power_in"))
      (node (ref "D15") (pin "8") (pinfunction "GND_8") (pintype "power_in"))
      (node (ref "D16") (pin "3") (pinfunction "GND_3") (pintype "power_in"))
      (node (ref "D16") (pin "8") (pinfunction "GND_8") (pintype "power_in"))
      (node (ref "D17") (pin "3") (pinfunction "GND_3") (pintype "power_in"))
      (node (ref "D17") (pin "8") (pinfunction "GND_8") (pintype "power_in"))
      (node (ref "D18") (pin "3") (pinfunction "GND_3") (pintype "power_in"))
      (node (ref "D18") (pin "8") (pinfunction "GND_8") (pintype "power_in"))
      (node (ref "D19") (pin "3") (pinfunction "GND_3") (pintype "power_in"))
      (node (ref "D19") (pin "8") (pinfunction "GND_8") (pintype "power_in"))
      (node (ref "D20") (pin "3") (pinfunction "GND_3") (pintype "power_in"))
      (node (ref "D20") (pin "8") (pinfunction "GND_8") (pintype "power_in"))
      (node (ref "D21") (pin "3") (pinfunction "GND_3") (pintype "power_in"))
      (node (ref "D21") (pin "8") (pinfunction "GND_8") (pintype "power_in"))
      (node (ref "D23") (pin "3") (pinfunction "GND_3") (pintype "power_in"))
      (node (ref "D23") (pin "8") (pinfunction "GND_8") (pintype "power_in"))
      (node (ref "D24") (pin "3") (pinfunction "GND_3") (pintype "power_in"))
      (node (ref "D24") (pin "8") (pinfunction "GND_8") (pintype "power_in"))
      (node (ref "D25") (pin "3") (pinfunction "GND_3") (pintype "power_in"))
      (node (ref "D25") (pin "8") (pinfunction "GND_8") (pintype "power_in"))
      (node (ref "D26") (pin "3") (pinfunction "GND_3") (pintype "power_in"))
      (node (ref "D26") (pin "8") (pinfunction "GND_8") (pintype "power_in"))
      (node (ref "D27") (pin "3") (pinfunction "GND_3") (pintype "power_in"))
      (node (ref "D27") (pin "8") (pinfunction "GND_8") (pintype "power_in"))
      (node (ref "D28") (pin "3") (pinfunction "GND_3") (pintype "power_in"))
      (node (ref "D28") (pin "8") (pinfunction "GND_8") (pintype "power_in"))
      (node (ref "D29") (pin "3") (pinfunction "GND_3") (pintype "power_in"))
      (node (ref "D29") (pin "8") (pinfunction "GND_8") (pintype "power_in"))
      (node (ref "J1") (pin "MH1") (pinfunction "MH1_MH1") (pintype "passive"))
      (node (ref "J1") (pin "MH2") (pinfunction "MH2_MH2") (pintype "passive"))
      (node (ref "J1") (pin "MH3") (pinfunction "MH3_MH3") (pintype "passive"))
      (node (ref "J1") (pin "MH4") (pinfunction "MH4_MH4") (pintype "passive"))
      (node (ref "J1") (pin "MH5") (pinfunction "MH5_MH5") (pintype "passive"))
      (node (ref "J11") (pin "1") (pinfunction "1_1") (pintype "passive"))
      (node (ref "J3") (pin "11") (pinfunction "11_11") (pintype "passive"))
      (node (ref "J3") (pin "14") (pinfunction "14_14") (pintype "passive"))
      (node (ref "J3") (pin "15") (pinfunction "15_15") (pintype "passive"))
      (node (ref "J3") (pin "18") (pinfunction "18_18") (pintype "passive"))
      (node (ref "J3") (pin "21") (pinfunction "21_21") (pintype "passive"))
      (node (ref "J3") (pin "3") (pinfunction "3_3") (pintype "passive"))
      (node (ref "J3") (pin "6") (pinfunction "6_6") (pintype "passive"))
      (node (ref "J3") (pin "7") (pinfunction "7_7") (pintype "passive"))
      (node (ref "J3") (pin "8") (pinfunction "8_8") (pintype "passive"))
      (node (ref "J4") (pin "MH1") (pinfunction "MH1_MH1") (pintype "passive"))
      (node (ref "J4") (pin "MH2") (pinfunction "MH2_MH2") (pintype "passive"))
      (node (ref "J4") (pin "MH3") (pinfunction "MH3_MH3") (pintype "passive"))
      (node (ref "J4") (pin "MH4") (pinfunction "MH4_MH4") (pintype "passive"))
      (node (ref "J4") (pin "MH5") (pinfunction "MH5_MH5") (pintype "passive"))
      (node (ref "J5") (pin "11") (pinfunction "GND_11") (pintype "passive"))
      (node (ref "J5") (pin "17") (pinfunction "GND_17") (pintype "power_in"))
      (node (ref "J5") (pin "2") (pinfunction "GND_2") (pintype "power_in"))
      (node (ref "J5") (pin "20") (pinfunction "MNT_1_20") (pintype "passive"))
      (node (ref "J5") (pin "21") (pinfunction "MNT_2_21") (pintype "passive"))
      (node (ref "J5") (pin "22") (pinfunction "MNT_3_22") (pintype "passive"))
      (node (ref "J5") (pin "5") (pinfunction "GND_5") (pintype "passive"))
      (node (ref "J5") (pin "8") (pinfunction "GND_8") (pintype "passive"))
      (node (ref "J6") (pin "10") (pinfunction "SHLD5_10") (pintype "passive"))
      (node (ref "J6") (pin "11") (pinfunction "SHLD6_11") (pintype "passive"))
      (node (ref "J6") (pin "5") (pinfunction "GND_5") (pintype "passive"))
      (node (ref "J6") (pin "6") (pinfunction "SHLD1_6") (pintype "passive"))
      (node (ref "J6") (pin "7") (pinfunction "SHLD2_7") (pintype "passive"))
      (node (ref "J6") (pin "8") (pinfunction "SHLD3_8") (pintype "passive"))
      (node (ref "J6") (pin "9") (pinfunction "SHLD4_9") (pintype "passive"))
      (node (ref "J7") (pin "2") (pinfunction "2_2") (pintype "passive"))
      (node (ref "J8") (pin "10") (pinfunction "MNT_6_10") (pintype "passive"))
      (node (ref "J8") (pin "11") (pinfunction "MNT_7_11") (pintype "passive"))
      (node (ref "J8") (pin "13") (pinfunction "13_13") (pintype "passive"))
      (node (ref "J8") (pin "5") (pinfunction "MNT_1_5") (pintype "passive"))
      (node (ref "J8") (pin "6") (pinfunction "MNT_2_6") (pintype "passive"))
      (node (ref "J8") (pin "7") (pinfunction "MNT_3_7") (pintype "passive"))
      (node (ref "J8") (pin "8") (pinfunction "MNT_4_8") (pintype "passive"))
      (node (ref "J8") (pin "9") (pinfunction "MNT_5_9") (pintype "passive"))
      (node (ref "J9") (pin "1") (pinfunction "1_1") (pintype "passive"))
      (node (ref "MH1") (pin "1") (pinfunction "MH_1") (pintype "passive"))
      (node (ref "MH1") (pin "2") (pinfunction "V1_2") (pintype "passive"))
      (node (ref "MH1") (pin "3") (pinfunction "V2_3") (pintype "passive"))
      (node (ref "MH1") (pin "4") (pinfunction "V3_4") (pintype "passive"))
      (node (ref "MH1") (pin "5") (pinfunction "V4_5") (pintype "passive"))
      (node (ref "MH1") (pin "6") (pinfunction "V5_6") (pintype "passive"))
      (node (ref "MH1") (pin "7") (pinfunction "V6_7") (pintype "passive"))
      (node (ref "MH10") (pin "1") (pinfunction "MH_1") (pintype "passive"))
      (node (ref "MH10") (pin "2") (pinfunction "V1_2") (pintype "passive"))
      (node (ref "MH10") (pin "3") (pinfunction "V2_3") (pintype "passive"))
      (node (ref "MH10") (pin "4") (pinfunction "V3_4") (pintype "passive"))
      (node (ref "MH10") (pin "5") (pinfunction "V4_5") (pintype "passive"))
      (node (ref "MH10") (pin "6") (pinfunction "V5_6") (pintype "passive"))
      (node (ref "MH10") (pin "7") (pinfunction "V6_7") (pintype "passive"))
      (node (ref "MH11") (pin "1") (pinfunction "MH_1") (pintype "passive"))
      (node (ref "MH11") (pin "2") (pinfunction "V1_2") (pintype "passive"))
      (node (ref "MH11") (pin "3") (pinfunction "V2_3") (pintype "passive"))
      (node (ref "MH11") (pin "4") (pinfunction "V3_4") (pintype "passive"))
      (node (ref "MH11") (pin "5") (pinfunction "V4_5") (pintype "passive"))
      (node (ref "MH11") (pin "6") (pinfunction "V5_6") (pintype "passive"))
      (node (ref "MH11") (pin "7") (pinfunction "V6_7") (pintype "passive"))
      (node (ref "MH12") (pin "1") (pinfunction "MH_1") (pintype "passive"))
      (node (ref "MH12") (pin "2") (pinfunction "V1_2") (pintype "passive"))
      (node (ref "MH12") (pin "3") (pinfunction "V2_3") (pintype "passive"))
      (node (ref "MH12") (pin "4") (pinfunction "V3_4") (pintype "passive"))
      (node (ref "MH12") (pin "5") (pinfunction "V4_5") (pintype "passive"))
      (node (ref "MH12") (pin "6") (pinfunction "V5_6") (pintype "passive"))
      (node (ref "MH12") (pin "7") (pinfunction "V6_7") (pintype "passive"))
      (node (ref "MH2") (pin "1") (pinfunction "MH_1") (pintype "passive"))
      (node (ref "MH2") (pin "2") (pinfunction "V1_2") (pintype "passive"))
      (node (ref "MH2") (pin "3") (pinfunction "V2_3") (pintype "passive"))
      (node (ref "MH2") (pin "4") (pinfunction "V3_4") (pintype "passive"))
      (node (ref "MH2") (pin "5") (pinfunction "V4_5") (pintype "passive"))
      (node (ref "MH2") (pin "6") (pinfunction "V5_6") (pintype "passive"))
      (node (ref "MH2") (pin "7") (pinfunction "V6_7") (pintype "passive"))
      (node (ref "MH3") (pin "1") (pinfunction "MH_1") (pintype "passive"))
      (node (ref "MH3") (pin "2") (pinfunction "V1_2") (pintype "passive"))
      (node (ref "MH3") (pin "3") (pinfunction "V2_3") (pintype "passive"))
      (node (ref "MH3") (pin "4") (pinfunction "V3_4") (pintype "passive"))
      (node (ref "MH3") (pin "5") (pinfunction "V4_5") (pintype "passive"))
      (node (ref "MH3") (pin "6") (pinfunction "V5_6") (pintype "passive"))
      (node (ref "MH3") (pin "7") (pinfunction "V6_7") (pintype "passive"))
      (node (ref "MH4") (pin "1") (pinfunction "MH_1") (pintype "passive"))
      (node (ref "MH4") (pin "2") (pinfunction "V1_2") (pintype "passive"))
      (node (ref "MH4") (pin "3") (pinfunction "V2_3") (pintype "passive"))
      (node (ref "MH4") (pin "4") (pinfunction "V3_4") (pintype "passive"))
      (node (ref "MH4") (pin "5") (pinfunction "V4_5") (pintype "passive"))
      (node (ref "MH4") (pin "6") (pinfunction "V5_6") (pintype "passive"))
      (node (ref "MH4") (pin "7") (pinfunction "V6_7") (pintype "passive"))
      (node (ref "MH5") (pin "1") (pinfunction "MH_1") (pintype "passive"))
      (node (ref "MH5") (pin "2") (pinfunction "V1_2") (pintype "passive"))
      (node (ref "MH5") (pin "3") (pinfunction "V2_3") (pintype "passive"))
      (node (ref "MH5") (pin "4") (pinfunction "V3_4") (pintype "passive"))
      (node (ref "MH5") (pin "5") (pinfunction "V4_5") (pintype "passive"))
      (node (ref "MH5") (pin "6") (pinfunction "V5_6") (pintype "passive"))
      (node (ref "MH5") (pin "7") (pinfunction "V6_7") (pintype "passive"))
      (node (ref "MH6") (pin "1") (pinfunction "MH_1") (pintype "passive"))
      (node (ref "MH6") (pin "2") (pinfunction "V1_2") (pintype "passive"))
      (node (ref "MH6") (pin "3") (pinfunction "V2_3") (pintype "passive"))
      (node (ref "MH6") (pin "4") (pinfunction "V3_4") (pintype "passive"))
      (node (ref "MH6") (pin "5") (pinfunction "V4_5") (pintype "passive"))
      (node (ref "MH6") (pin "6") (pinfunction "V5_6") (pintype "passive"))
      (node (ref "MH6") (pin "7") (pinfunction "V6_7") (pintype "passive"))
      (node (ref "MH7") (pin "1") (pinfunction "MH_1") (pintype "passive"))
      (node (ref "MH7") (pin "2") (pinfunction "V1_2") (pintype "passive"))
      (node (ref "MH7") (pin "3") (pinfunction "V2_3") (pintype "passive"))
      (node (ref "MH7") (pin "4") (pinfunction "V3_4") (pintype "passive"))
      (node (ref "MH7") (pin "5") (pinfunction "V4_5") (pintype "passive"))
      (node (ref "MH7") (pin "6") (pinfunction "V5_6") (pintype "passive"))
      (node (ref "MH7") (pin "7") (pinfunction "V6_7") (pintype "passive"))
      (node (ref "MH8") (pin "1") (pinfunction "MH_1") (pintype "passive"))
      (node (ref "MH8") (pin "2") (pinfunction "V1_2") (pintype "passive"))
      (node (ref "MH8") (pin "3") (pinfunction "V2_3") (pintype "passive"))
      (node (ref "MH8") (pin "4") (pinfunction "V3_4") (pintype "passive"))
      (node (ref "MH8") (pin "5") (pinfunction "V4_5") (pintype "passive"))
      (node (ref "MH8") (pin "6") (pinfunction "V5_6") (pintype "passive"))
      (node (ref "MH8") (pin "7") (pinfunction "V6_7") (pintype "passive"))
      (node (ref "MH9") (pin "1") (pinfunction "MH_1") (pintype "passive"))
      (node (ref "MH9") (pin "2") (pinfunction "V1_2") (pintype "passive"))
      (node (ref "MH9") (pin "3") (pinfunction "V2_3") (pintype "passive"))
      (node (ref "MH9") (pin "4") (pinfunction "V3_4") (pintype "passive"))
      (node (ref "MH9") (pin "5") (pinfunction "V4_5") (pintype "passive"))
      (node (ref "MH9") (pin "6") (pinfunction "V5_6") (pintype "passive"))
      (node (ref "MH9") (pin "7") (pinfunction "V6_7") (pintype "passive"))
      (node (ref "Q24") (pin "1") (pinfunction "Source1_1") (pintype "passive"))
      (node (ref "Q24") (pin "4") (pinfunction "Source2_4") (pintype "passive"))
      (node (ref "Q25") (pin "1") (pinfunction "Source1_1") (pintype "passive"))
      (node (ref "Q25") (pin "4") (pinfunction "Source2_4") (pintype "passive"))
      (node (ref "Q26") (pin "2") (pinfunction "S_2") (pintype "passive"))
      (node (ref "Q27") (pin "4") (pinfunction "Source2_4") (pintype "passive"))
      (node (ref "Q28") (pin "4") (pinfunction "Source2_4") (pintype "passive"))
      (node (ref "R138") (pin "1") (pinfunction "1_1") (pintype "passive"))
      (node (ref "R139") (pin "1") (pinfunction "1_1") (pintype "passive"))
      (node (ref "R140") (pin "1") (pinfunction "1_1") (pintype "passive"))
      (node (ref "R141") (pin "1") (pinfunction "1_1") (pintype "passive"))
      (node (ref "R144") (pin "1") (pinfunction "1_1") (pintype "passive"))
      (node (ref "R146") (pin "1") (pinfunction "1_1") (pintype "passive"))
      (node (ref "R150") (pin "1") (pinfunction "1_1") (pintype "passive"))
      (node (ref "R167") (pin "1") (pinfunction "1_1") (pintype "passive"))
      (node (ref "R180") (pin "1") (pinfunction "1_1") (pintype "passive"))
      (node (ref "R181") (pin "1") (pinfunction "1_1") (pintype "passive"))
      (node (ref "U15") (pin "2") (pinfunction "GND_2") (pintype "power_in"))
      (node (ref "U16") (pin "2") (pinfunction "GND_2") (pintype "power_in"))
      (node (ref "U17") (pin "2") (pinfunction "GND_2") (pintype "power_in"))
      (node (ref "U18") (pin "1") (pinfunction "~{OE}_1") (pintype "input"))
      (node (ref "U18") (pin "3") (pinfunction "GND_3") (pintype "power_in"))
      (node (ref "U19") (pin "2") (pinfunction "GND_2") (pintype "power_in"))
      (node (ref "U20") (pin "1") (pinfunction "~{OE}_1") (pintype "input"))
      (node (ref "U20") (pin "3") (pinfunction "GND_3") (pintype "power_in"))
    )
    (net (code "298") (name "JSN_1V8_REF") (class "Default")
      (node (ref "C164") (pin "1") (pinfunction "1_1") (pintype "passive"))
      (node (ref "Q27") (pin "2") (pinfunction "Gate1_2") (pintype "passive"))
      (node (ref "Q28") (pin "2") (pinfunction "Gate1_2") (pintype "passive"))
      (node (ref "R143") (pin "2") (pinfunction "2_2") (pintype "passive"))
      (node (ref "R165") (pin "2") (pinfunction "2_2") (pintype "passive"))
      (node (ref "R170") (pin "2") (pinfunction "2_2") (pintype "passive"))
      (node (ref "R171") (pin "2") (pinfunction "2_2") (pintype "passive"))
      (node (ref "R182") (pin "1") (pinfunction "1_1") (pintype "passive"))
      (node (ref "U20") (pin "5") (pinfunction "VCC_5") (pintype "power_in"))
    )
    (net (code "299") (name "Net-(D14-A)") (class "Default")
      (node (ref "D14") (pin "2") (pinfunction "A_2") (pintype "passive"))
      (node (ref "R142") (pin "1") (pinfunction "1_1") (pintype "passive"))
    )
    (net (code "300") (name "Net-(F21-Pad2)") (class "Default")
      (node (ref "F21") (pin "2") (pinfunction "2_2") (pintype "passive"))
      (node (ref "J9") (pin "2") (pinfunction "2_2") (pintype "passive"))
    )
    (net (code "301") (name "Net-(F22-Pad2)") (class "Default")
      (node (ref "F22") (pin "2") (pinfunction "2_2") (pintype "passive"))
      (node (ref "J11") (pin "2") (pinfunction "2_2") (pintype "passive"))
    )
    (net (code "302") (name "Net-(J7-Pad1)") (class "Default")
      (node (ref "J7") (pin "1") (pinfunction "1_1") (pintype "passive"))
      (node (ref "R164") (pin "2") (pinfunction "2_2") (pintype "passive"))
    )
    (net (code "303") (name "Net-(J10-1_ANODE_GREEN{slash}1_CATHODE_YELLOW)") (class "Default")
      (node (ref "J10") (pin "P11") (pinfunction "1_ANODE_GREEN/1_CATHODE_YELLOW_P11") (pintype "passive"))
      (node (ref "R174") (pin "1") (pinfunction "1_1") (pintype "passive"))
    )
    (net (code "304") (name "Net-(J10-2_CATHODE_GREEN{slash}2_ANODE_YELLOW)") (class "Default")
      (node (ref "J10") (pin "P14") (pinfunction "2_CATHODE_GREEN/2_ANODE_YELLOW_P14") (pintype "passive"))
      (node (ref "R177") (pin "1") (pinfunction "1_1") (pintype "passive"))
    )
    (net (code "305") (name "Net-(Q25A-Gate1)") (class "Default")
      (node (ref "Q25") (pin "2") (pinfunction "Gate1_2") (pintype "passive"))
      (node (ref "R149") (pin "1") (pinfunction "1_1") (pintype "passive"))
      (node (ref "R150") (pin "2") (pinfunction "2_2") (pintype "passive"))
    )
    (net (code "306") (name "Net-(Q26-D)") (class "Default")
      (node (ref "Q26") (pin "3") (pinfunction "D_3") (pintype "passive"))
      (node (ref "R165") (pin "1") (pinfunction "1_1") (pintype "passive"))
      (node (ref "R166") (pin "1") (pinfunction "1_1") (pintype "passive"))
    )
    (net (code "307") (name "Net-(Q27A-Source1)") (class "Default")
      (node (ref "Q27") (pin "1") (pinfunction "Source1_1") (pintype "passive"))
      (node (ref "R170") (pin "1") (pinfunction "1_1") (pintype "passive"))
      (node (ref "R172") (pin "1") (pinfunction "1_1") (pintype "passive"))
    )
    (net (code "308") (name "Net-(Q27B-Gate2)") (class "Default")
      (node (ref "Q27") (pin "5") (pinfunction "Gate2_5") (pintype "passive"))
      (node (ref "R178") (pin "1") (pinfunction "1_1") (pintype "passive"))
      (node (ref "R180") (pin "2") (pinfunction "2_2") (pintype "passive"))
    )
    (net (code "309") (name "Net-(Q28A-Source1)") (class "Default")
      (node (ref "Q28") (pin "1") (pinfunction "Source1_1") (pintype "passive"))
      (node (ref "R171") (pin "1") (pinfunction "1_1") (pintype "passive"))
      (node (ref "R173") (pin "1") (pinfunction "1_1") (pintype "passive"))
    )
    (net (code "310") (name "Net-(Q28B-Gate2)") (class "Default")
      (node (ref "Q28") (pin "5") (pinfunction "Gate2_5") (pintype "passive"))
      (node (ref "R179") (pin "1") (pinfunction "1_1") (pintype "passive"))
      (node (ref "R181") (pin "2") (pinfunction "2_2") (pintype "passive"))
    )
    (net (code "311") (name "Net-(U15-EN)") (class "Default")
      (node (ref "R139") (pin "2") (pinfunction "2_2") (pintype "passive"))
      (node (ref "U15") (pin "4") (pinfunction "EN_4") (pintype "input"))
    )
    (net (code "312") (name "Net-(U16-EN)") (class "Default")
      (node (ref "R141") (pin "2") (pinfunction "2_2") (pintype "passive"))
      (node (ref "U16") (pin "4") (pinfunction "EN_4") (pintype "input"))
    )
    (net (code "313") (name "Net-(U18A-Y)") (class "Default")
      (node (ref "R147") (pin "1") (pinfunction "1_1") (pintype "passive"))
      (node (ref "U18") (pin "4") (pinfunction "Y_4") (pintype "tri_state"))
    )
    (net (code "314") (name "Net-(U20A-A)") (class "Default")
      (node (ref "R182") (pin "2") (pinfunction "2_2") (pintype "passive"))
      (node (ref "R183") (pin "1") (pinfunction "1_1") (pintype "passive"))
      (node (ref "R184") (pin "1") (pinfunction "1_1") (pintype "passive"))
      (node (ref "U20") (pin "2") (pinfunction "A_2") (pintype "input"))
    )
    (net (code "315") (name "PRE_VCC") (class "Default")
      (node (ref "R148") (pin "2") (pinfunction "2_2") (pintype "passive"))
    )
    (net (code "316") (name "unconnected-(D15-IO1-Pad1)") (class "Default")
      (node (ref "D15") (pin "1") (pinfunction "IO1_1") (pintype "bidirectional"))
    )
    (net (code "317") (name "unconnected-(D15-IO2-Pad2)") (class "Default")
      (node (ref "D15") (pin "2") (pinfunction "IO2_2") (pintype "bidirectional"))
    )
    (net (code "318") (name "unconnected-(D15-IO3-Pad4)") (class "Default")
      (node (ref "D15") (pin "4") (pinfunction "IO3_4") (pintype "bidirectional"))
    )
    (net (code "319") (name "unconnected-(D15-IO4-Pad5)") (class "Default")
      (node (ref "D15") (pin "5") (pinfunction "IO4_5") (pintype "bidirectional"))
    )
    (net (code "320") (name "unconnected-(D15-NC-Pad6)") (class "Default")
      (node (ref "D15") (pin "6") (pinfunction "NC_6") (pintype "passive"))
    )
    (net (code "321") (name "unconnected-(D15-NC-Pad7)") (class "Default")
      (node (ref "D15") (pin "7") (pinfunction "NC_7") (pintype "passive"))
    )
    (net (code "322") (name "unconnected-(D15-NC-Pad9)") (class "Default")
      (node (ref "D15") (pin "9") (pinfunction "NC_9") (pintype "passive"))
    )
    (net (code "323") (name "unconnected-(D15-NC-Pad10)") (class "Default")
      (node (ref "D15") (pin "10") (pinfunction "NC_10") (pintype "passive"))
    )
    (net (code "324") (name "unconnected-(D16-IO1-Pad1)") (class "Default")
      (node (ref "D16") (pin "1") (pinfunction "IO1_1") (pintype "bidirectional"))
    )
    (net (code "325") (name "unconnected-(D16-IO2-Pad2)") (class "Default")
      (node (ref "D16") (pin "2") (pinfunction "IO2_2") (pintype "bidirectional"))
    )
    (net (code "326") (name "unconnected-(D16-IO3-Pad4)") (class "Default")
      (node (ref "D16") (pin "4") (pinfunction "IO3_4") (pintype "bidirectional"))
    )
    (net (code "327") (name "unconnected-(D16-IO4-Pad5)") (class "Default")
      (node (ref "D16") (pin "5") (pinfunction "IO4_5") (pintype "bidirectional"))
    )
    (net (code "328") (name "unconnected-(D16-NC-Pad6)") (class "Default")
      (node (ref "D16") (pin "6") (pinfunction "NC_6") (pintype "passive"))
    )
    (net (code "329") (name "unconnected-(D16-NC-Pad7)") (class "Default")
      (node (ref "D16") (pin "7") (pinfunction "NC_7") (pintype "passive"))
    )
    (net (code "330") (name "unconnected-(D16-NC-Pad9)") (class "Default")
      (node (ref "D16") (pin "9") (pinfunction "NC_9") (pintype "passive"))
    )
    (net (code "331") (name "unconnected-(D16-NC-Pad10)") (class "Default")
      (node (ref "D16") (pin "10") (pinfunction "NC_10") (pintype "passive"))
    )
    (net (code "332") (name "unconnected-(D17-IO1-Pad1)") (class "Default")
      (node (ref "D17") (pin "1") (pinfunction "IO1_1") (pintype "bidirectional"))
    )
    (net (code "333") (name "unconnected-(D17-IO2-Pad2)") (class "Default")
      (node (ref "D17") (pin "2") (pinfunction "IO2_2") (pintype "bidirectional"))
    )
    (net (code "334") (name "unconnected-(D17-IO3-Pad4)") (class "Default")
      (node (ref "D17") (pin "4") (pinfunction "IO3_4") (pintype "bidirectional"))
    )
    (net (code "335") (name "unconnected-(D17-IO4-Pad5)") (class "Default")
      (node (ref "D17") (pin "5") (pinfunction "IO4_5") (pintype "bidirectional"))
    )
    (net (code "336") (name "unconnected-(D17-NC-Pad6)") (class "Default")
      (node (ref "D17") (pin "6") (pinfunction "NC_6") (pintype "passive"))
    )
    (net (code "337") (name "unconnected-(D17-NC-Pad7)") (class "Default")
      (node (ref "D17") (pin "7") (pinfunction "NC_7") (pintype "passive"))
    )
    (net (code "338") (name "unconnected-(D17-NC-Pad9)") (class "Default")
      (node (ref "D17") (pin "9") (pinfunction "NC_9") (pintype "passive"))
    )
    (net (code "339") (name "unconnected-(D17-NC-Pad10)") (class "Default")
      (node (ref "D17") (pin "10") (pinfunction "NC_10") (pintype "passive"))
    )
    (net (code "340") (name "unconnected-(D18-IO1-Pad1)") (class "Default")
      (node (ref "D18") (pin "1") (pinfunction "IO1_1") (pintype "bidirectional"))
    )
    (net (code "341") (name "unconnected-(D18-IO2-Pad2)") (class "Default")
      (node (ref "D18") (pin "2") (pinfunction "IO2_2") (pintype "bidirectional"))
    )
    (net (code "342") (name "unconnected-(D18-IO3-Pad4)") (class "Default")
      (node (ref "D18") (pin "4") (pinfunction "IO3_4") (pintype "bidirectional"))
    )
    (net (code "343") (name "unconnected-(D18-IO4-Pad5)") (class "Default")
      (node (ref "D18") (pin "5") (pinfunction "IO4_5") (pintype "bidirectional"))
    )
    (net (code "344") (name "unconnected-(D18-NC-Pad6)") (class "Default")
      (node (ref "D18") (pin "6") (pinfunction "NC_6") (pintype "passive"))
    )
    (net (code "345") (name "unconnected-(D18-NC-Pad7)") (class "Default")
      (node (ref "D18") (pin "7") (pinfunction "NC_7") (pintype "passive"))
    )
    (net (code "346") (name "unconnected-(D18-NC-Pad9)") (class "Default")
      (node (ref "D18") (pin "9") (pinfunction "NC_9") (pintype "passive"))
    )
    (net (code "347") (name "unconnected-(D18-NC-Pad10)") (class "Default")
      (node (ref "D18") (pin "10") (pinfunction "NC_10") (pintype "passive"))
    )
    (net (code "348") (name "unconnected-(D23-IO4-Pad5)") (class "Default")
      (node (ref "D23") (pin "5") (pinfunction "IO4_5") (pintype "bidirectional"))
    )
    (net (code "349") (name "unconnected-(D23-NC-Pad6)") (class "Default")
      (node (ref "D23") (pin "6") (pinfunction "NC_6") (pintype "passive"))
    )
    (net (code "350") (name "unconnected-(D23-NC-Pad7)") (class "Default")
      (node (ref "D23") (pin "7") (pinfunction "NC_7") (pintype "passive"))
    )
    (net (code "351") (name "unconnected-(D23-NC-Pad9)") (class "Default")
      (node (ref "D23") (pin "9") (pinfunction "NC_9") (pintype "passive"))
    )
    (net (code "352") (name "unconnected-(D23-NC-Pad10)") (class "Default")
      (node (ref "D23") (pin "10") (pinfunction "NC_10") (pintype "passive"))
    )
    (net (code "353") (name "unconnected-(D24-IO1-Pad1)") (class "Default")
      (node (ref "D24") (pin "1") (pinfunction "IO1_1") (pintype "bidirectional"))
    )
    (net (code "354") (name "unconnected-(D24-IO2-Pad2)") (class "Default")
      (node (ref "D24") (pin "2") (pinfunction "IO2_2") (pintype "bidirectional"))
    )
    (net (code "355") (name "unconnected-(D24-IO3-Pad4)") (class "Default")
      (node (ref "D24") (pin "4") (pinfunction "IO3_4") (pintype "bidirectional"))
    )
    (net (code "356") (name "unconnected-(D24-IO4-Pad5)") (class "Default")
      (node (ref "D24") (pin "5") (pinfunction "IO4_5") (pintype "bidirectional"))
    )
    (net (code "357") (name "unconnected-(D24-NC-Pad6)") (class "Default")
      (node (ref "D24") (pin "6") (pinfunction "NC_6") (pintype "passive"))
    )
    (net (code "358") (name "unconnected-(D24-NC-Pad7)") (class "Default")
      (node (ref "D24") (pin "7") (pinfunction "NC_7") (pintype "passive"))
    )
    (net (code "359") (name "unconnected-(D24-NC-Pad9)") (class "Default")
      (node (ref "D24") (pin "9") (pinfunction "NC_9") (pintype "passive"))
    )
    (net (code "360") (name "unconnected-(D24-NC-Pad10)") (class "Default")
      (node (ref "D24") (pin "10") (pinfunction "NC_10") (pintype "passive"))
    )
    (net (code "361") (name "unconnected-(D25-IO1-Pad1)") (class "Default")
      (node (ref "D25") (pin "1") (pinfunction "IO1_1") (pintype "bidirectional"))
    )
    (net (code "362") (name "unconnected-(D25-IO2-Pad2)") (class "Default")
      (node (ref "D25") (pin "2") (pinfunction "IO2_2") (pintype "bidirectional"))
    )
    (net (code "363") (name "unconnected-(D25-IO3-Pad4)") (class "Default")
      (node (ref "D25") (pin "4") (pinfunction "IO3_4") (pintype "bidirectional"))
    )
    (net (code "364") (name "unconnected-(D25-IO4-Pad5)") (class "Default")
      (node (ref "D25") (pin "5") (pinfunction "IO4_5") (pintype "bidirectional"))
    )
    (net (code "365") (name "unconnected-(D25-NC-Pad6)") (class "Default")
      (node (ref "D25") (pin "6") (pinfunction "NC_6") (pintype "passive"))
    )
    (net (code "366") (name "unconnected-(D25-NC-Pad7)") (class "Default")
      (node (ref "D25") (pin "7") (pinfunction "NC_7") (pintype "passive"))
    )
    (net (code "367") (name "unconnected-(D25-NC-Pad9)") (class "Default")
      (node (ref "D25") (pin "9") (pinfunction "NC_9") (pintype "passive"))
    )
    (net (code "368") (name "unconnected-(D25-NC-Pad10)") (class "Default")
      (node (ref "D25") (pin "10") (pinfunction "NC_10") (pintype "passive"))
    )
    (net (code "369") (name "unconnected-(D26-IO1-Pad1)") (class "Default")
      (node (ref "D26") (pin "1") (pinfunction "IO1_1") (pintype "bidirectional"))
    )
    (net (code "370") (name "unconnected-(D26-IO2-Pad2)") (class "Default")
      (node (ref "D26") (pin "2") (pinfunction "IO2_2") (pintype "bidirectional"))
    )
    (net (code "371") (name "unconnected-(D26-IO3-Pad4)") (class "Default")
      (node (ref "D26") (pin "4") (pinfunction "IO3_4") (pintype "bidirectional"))
    )
    (net (code "372") (name "unconnected-(D26-IO4-Pad5)") (class "Default")
      (node (ref "D26") (pin "5") (pinfunction "IO4_5") (pintype "bidirectional"))
    )
    (net (code "373") (name "unconnected-(D26-NC-Pad6)") (class "Default")
      (node (ref "D26") (pin "6") (pinfunction "NC_6") (pintype "passive"))
    )
    (net (code "374") (name "unconnected-(D26-NC-Pad7)") (class "Default")
      (node (ref "D26") (pin "7") (pinfunction "NC_7") (pintype "passive"))
    )
    (net (code "375") (name "unconnected-(D26-NC-Pad9)") (class "Default")
      (node (ref "D26") (pin "9") (pinfunction "NC_9") (pintype "passive"))
    )
    (net (code "376") (name "unconnected-(D26-NC-Pad10)") (class "Default")
      (node (ref "D26") (pin "10") (pinfunction "NC_10") (pintype "passive"))
    )
    (net (code "377") (name "unconnected-(D27-NC-Pad6)") (class "Default")
      (node (ref "D27") (pin "6") (pinfunction "NC_6") (pintype "passive"))
    )
    (net (code "378") (name "unconnected-(D27-NC-Pad7)") (class "Default")
      (node (ref "D27") (pin "7") (pinfunction "NC_7") (pintype "passive"))
    )
    (net (code "379") (name "unconnected-(D27-NC-Pad9)") (class "Default")
      (node (ref "D27") (pin "9") (pinfunction "NC_9") (pintype "passive"))
    )
    (net (code "380") (name "unconnected-(D27-NC-Pad10)") (class "Default")
      (node (ref "D27") (pin "10") (pinfunction "NC_10") (pintype "passive"))
    )
    (net (code "381") (name "unconnected-(D28-NC-Pad6)") (class "Default")
      (node (ref "D28") (pin "6") (pinfunction "NC_6") (pintype "passive"))
    )
    (net (code "382") (name "unconnected-(D28-NC-Pad7)") (class "Default")
      (node (ref "D28") (pin "7") (pinfunction "NC_7") (pintype "passive"))
    )
    (net (code "383") (name "unconnected-(D28-NC-Pad9)") (class "Default")
      (node (ref "D28") (pin "9") (pinfunction "NC_9") (pintype "passive"))
    )
    (net (code "384") (name "unconnected-(D28-NC-Pad10)") (class "Default")
      (node (ref "D28") (pin "10") (pinfunction "NC_10") (pintype "passive"))
    )
    (net (code "385") (name "unconnected-(D29-NC-Pad6)") (class "Default")
      (node (ref "D29") (pin "6") (pinfunction "NC_6") (pintype "passive"))
    )
    (net (code "386") (name "unconnected-(D29-NC-Pad7)") (class "Default")
      (node (ref "D29") (pin "7") (pinfunction "NC_7") (pintype "passive"))
    )
    (net (code "387") (name "unconnected-(D29-NC-Pad9)") (class "Default")
      (node (ref "D29") (pin "9") (pinfunction "NC_9") (pintype "passive"))
    )
    (net (code "388") (name "unconnected-(D29-NC-Pad10)") (class "Default")
      (node (ref "D29") (pin "10") (pinfunction "NC_10") (pintype "passive"))
    )
    (net (code "389") (name "unconnected-(J5-RSVD-Pad14)") (class "Default")
      (node (ref "J5") (pin "14") (pinfunction "RSVD_14") (pintype "bidirectional+no_connect"))
    )
    (net (code "390") (name "unconnected-(J6-ID-Pad4)") (class "Default")
      (node (ref "J6") (pin "4") (pinfunction "ID_4") (pintype "passive+no_connect"))
    )
    (net (code "391") (name "unconnected-(Q23A-Drain1-Pad6)") (class "Default")
      (node (ref "Q23") (pin "6") (pinfunction "Drain1_6") (pintype "passive"))
    )
    (net (code "392") (name "unconnected-(Q23A-Gate1-Pad2)") (class "Default")
      (node (ref "Q23") (pin "2") (pinfunction "Gate1_2") (pintype "passive"))
    )
    (net (code "393") (name "unconnected-(Q23A-Source1-Pad1)") (class "Default")
      (node (ref "Q23") (pin "1") (pinfunction "Source1_1") (pintype "passive"))
    )
    (net (code "394") (name "unconnected-(Q23B-Drain2-Pad3)") (class "Default")
      (node (ref "Q23") (pin "3") (pinfunction "Drain2_3") (pintype "passive"))
    )
    (net (code "395") (name "unconnected-(Q23B-Gate2-Pad5)") (class "Default")
      (node (ref "Q23") (pin "5") (pinfunction "Gate2_5") (pintype "passive"))
    )
    (net (code "396") (name "unconnected-(Q23B-Source2-Pad4)") (class "Default")
      (node (ref "Q23") (pin "4") (pinfunction "Source2_4") (pintype "passive"))
    )
    (net (code "397") (name "unconnected-(Q24A-Drain1-Pad6)") (class "Default")
      (node (ref "Q24") (pin "6") (pinfunction "Drain1_6") (pintype "passive"))
    )
    (net (code "398") (name "unconnected-(Q24B-Drain2-Pad3)") (class "Default")
      (node (ref "Q24") (pin "3") (pinfunction "Drain2_3") (pintype "passive"))
    )
    (net (code "399") (name "unconnected-(Q25B-Drain2-Pad3)") (class "Default")
      (node (ref "Q25") (pin "3") (pinfunction "Drain2_3") (pintype "passive"))
    )
    (net (code "400") (name "unconnected-(U15-nFLG-Pad3)") (class "Default")
      (node (ref "U15") (pin "3") (pinfunction "nFLG_3") (pintype "output+no_connect"))
    )
    (net (code "401") (name "unconnected-(U16-nFLG-Pad3)") (class "Default")
      (node (ref "U16") (pin "3") (pinfunction "nFLG_3") (pintype "output+no_connect"))
    )
    (net (code "402") (name "unconnected-(U17-nFLG-Pad3)") (class "Default")
      (node (ref "U17") (pin "3") (pinfunction "nFLG_3") (pintype "output+no_connect"))
    )
    (net (code "403") (name "unconnected-(U19-nFLG-Pad3)") (class "Default")
      (node (ref "U19") (pin "3") (pinfunction "nFLG_3") (pintype "output+no_connect"))
    )
  )
)
